# BMS_Master.net
KiCad netlist of a schematic drawn in EAGLE
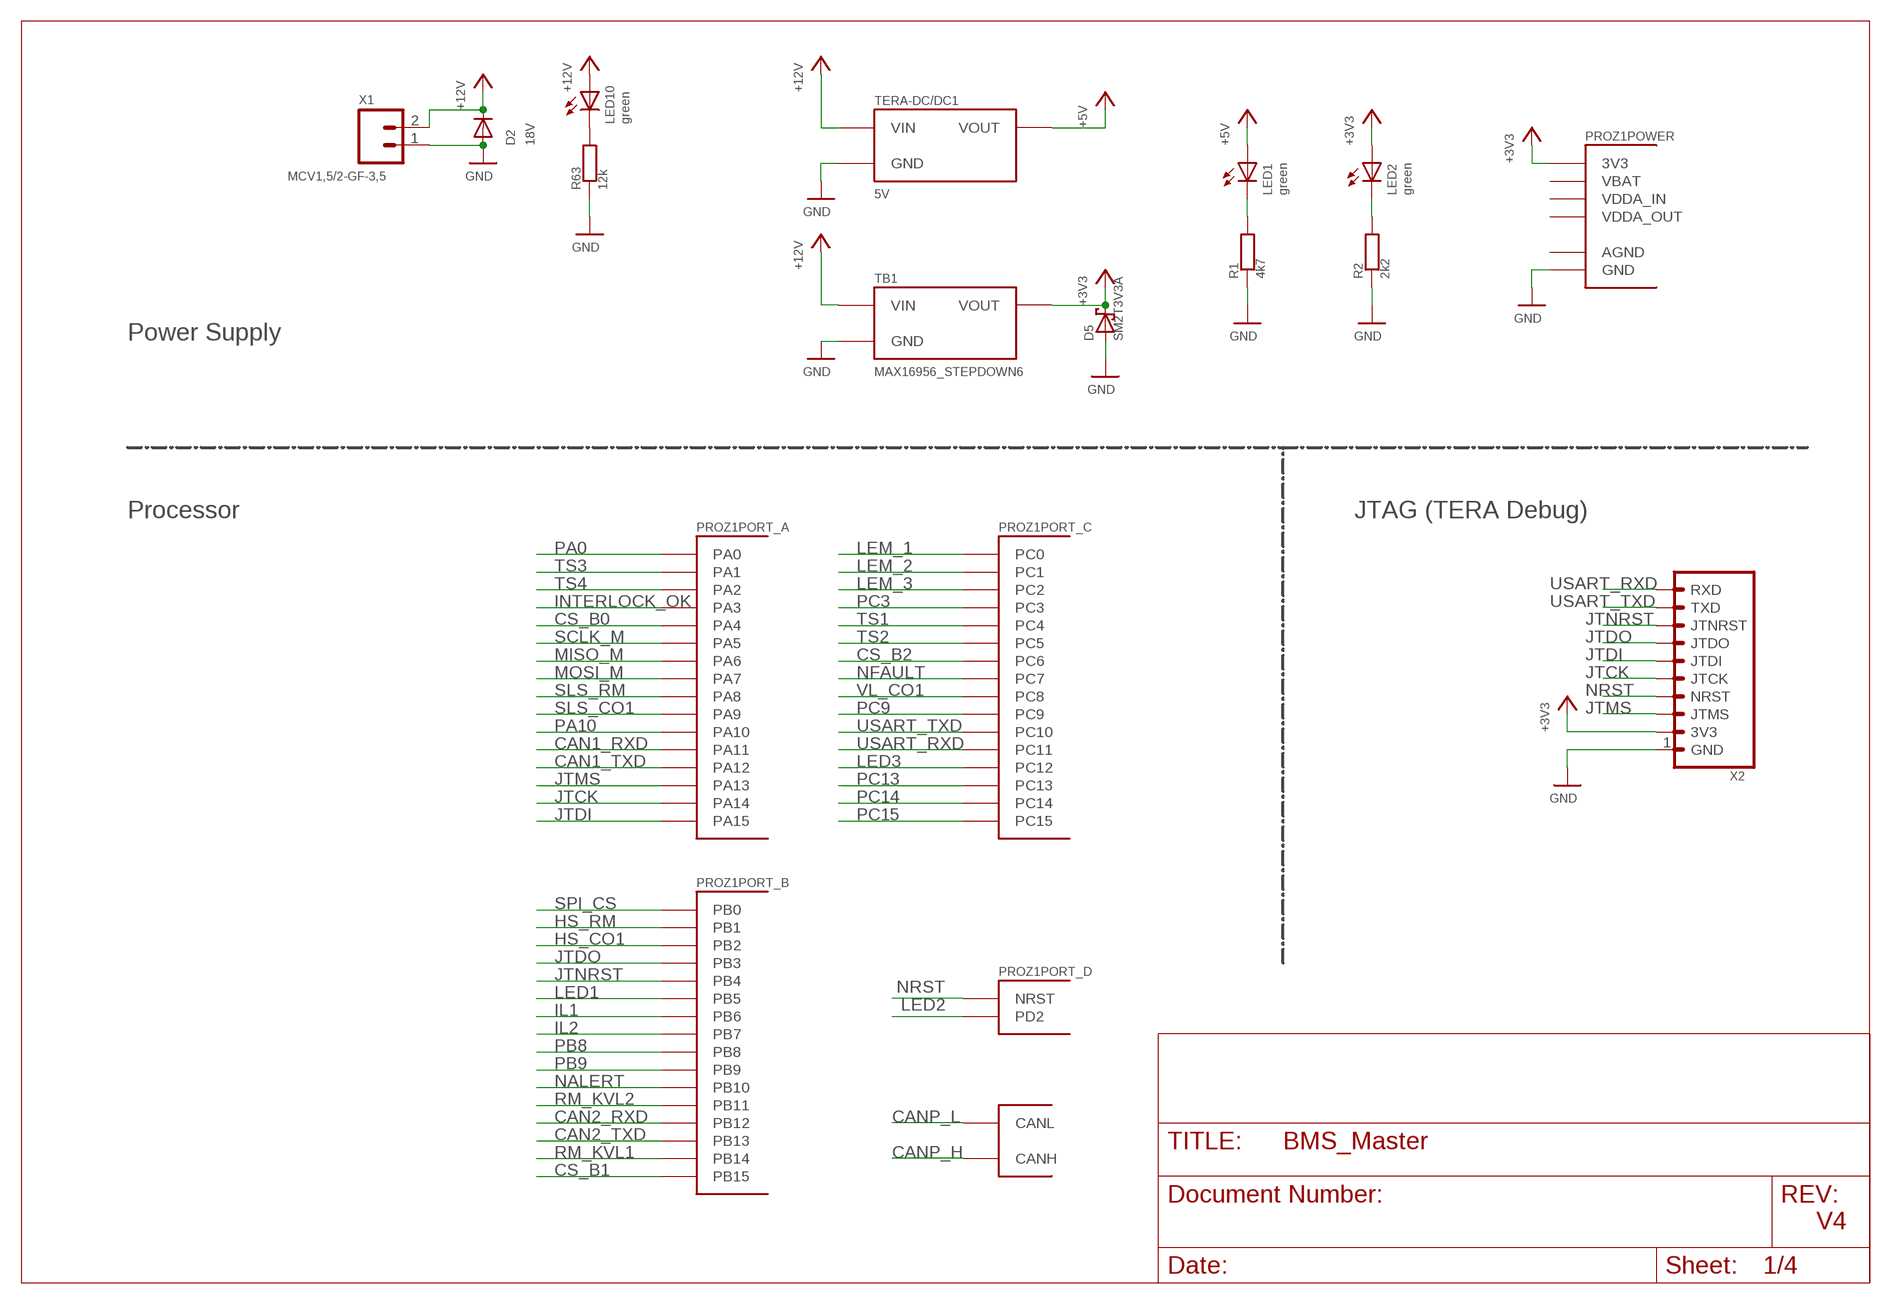
[diagram p0: schematic, sheet 1]
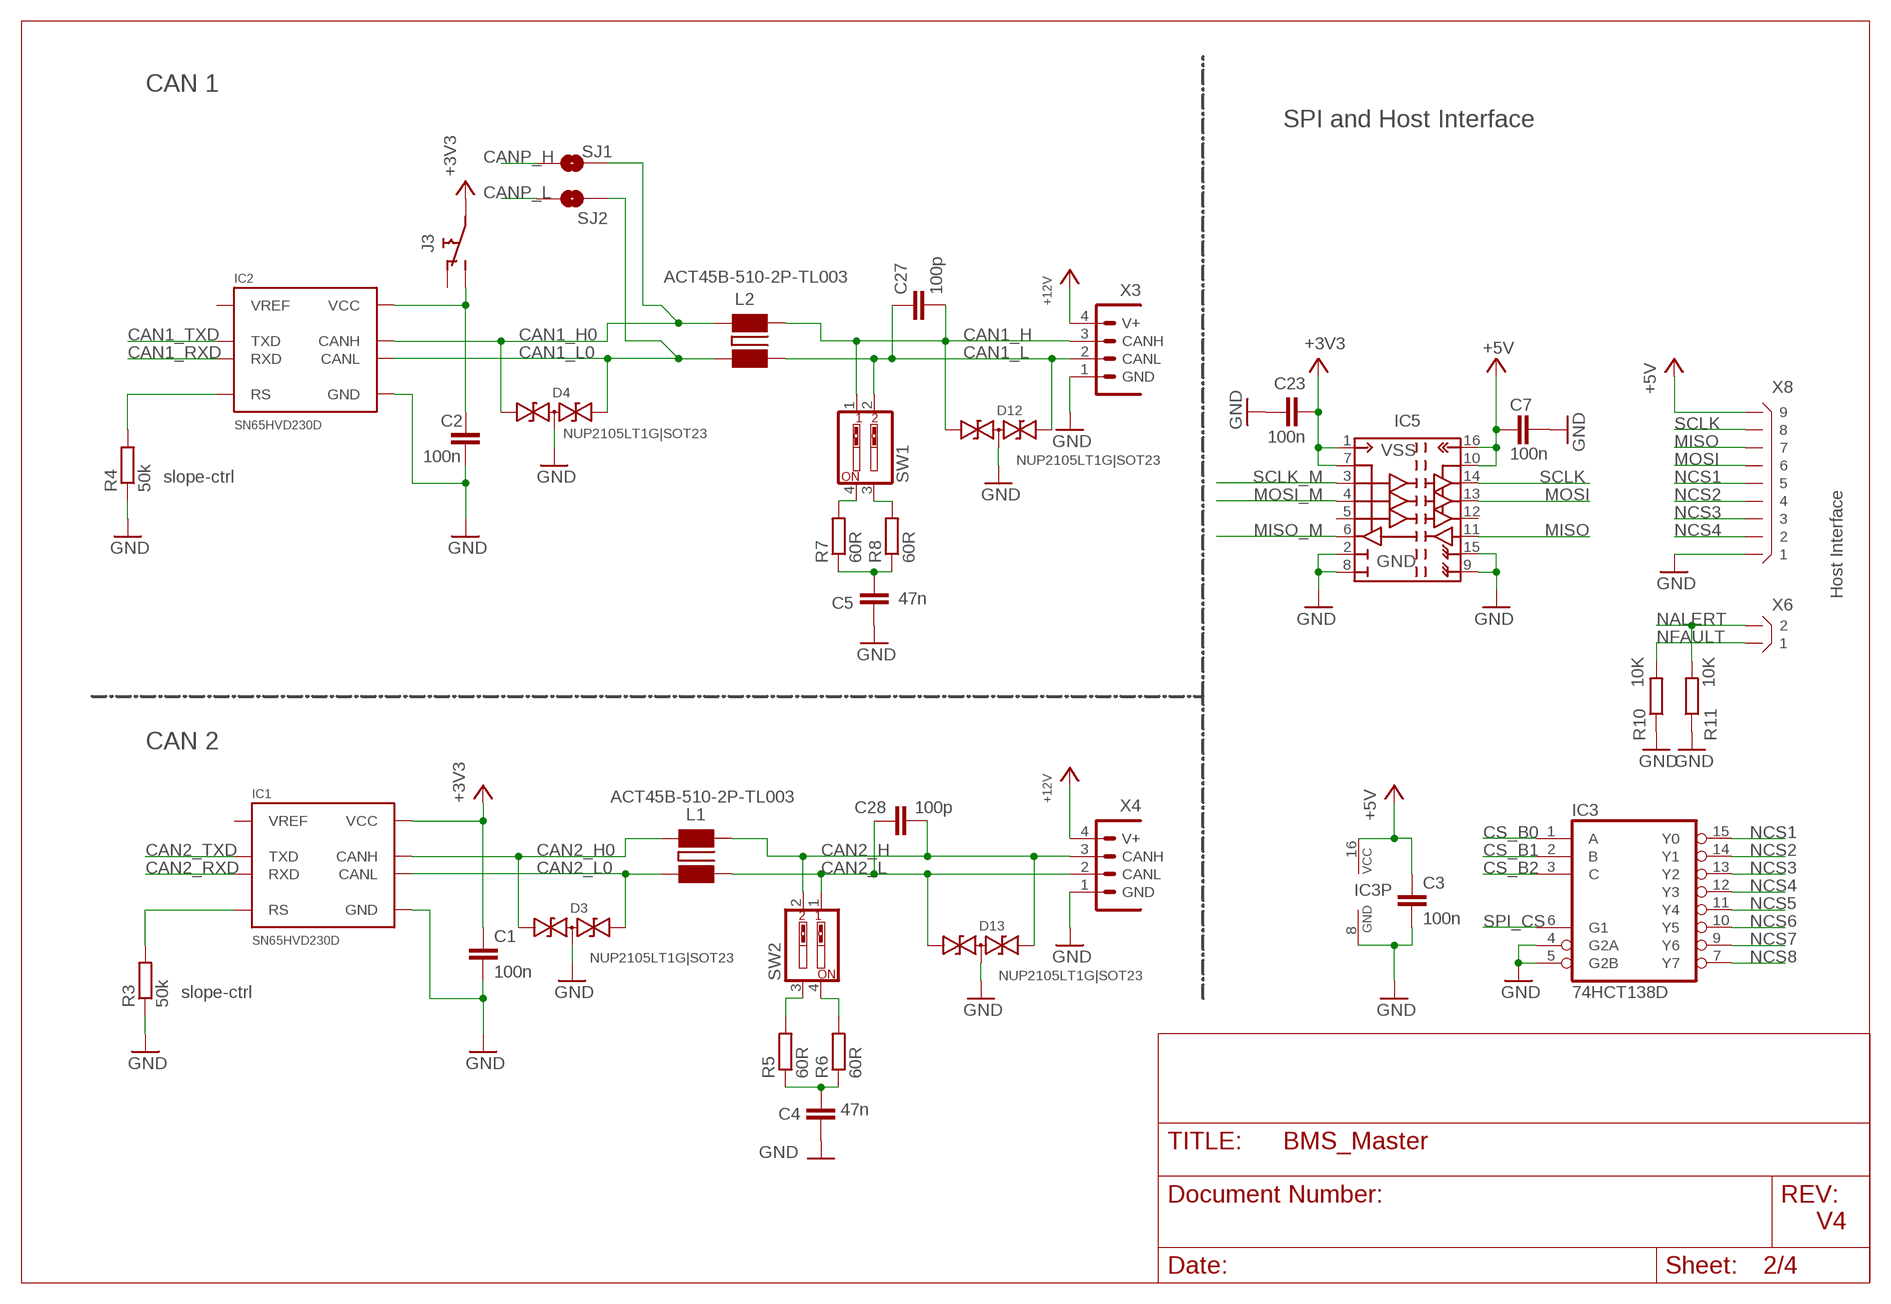
[diagram p1: schematic, sheet 2]
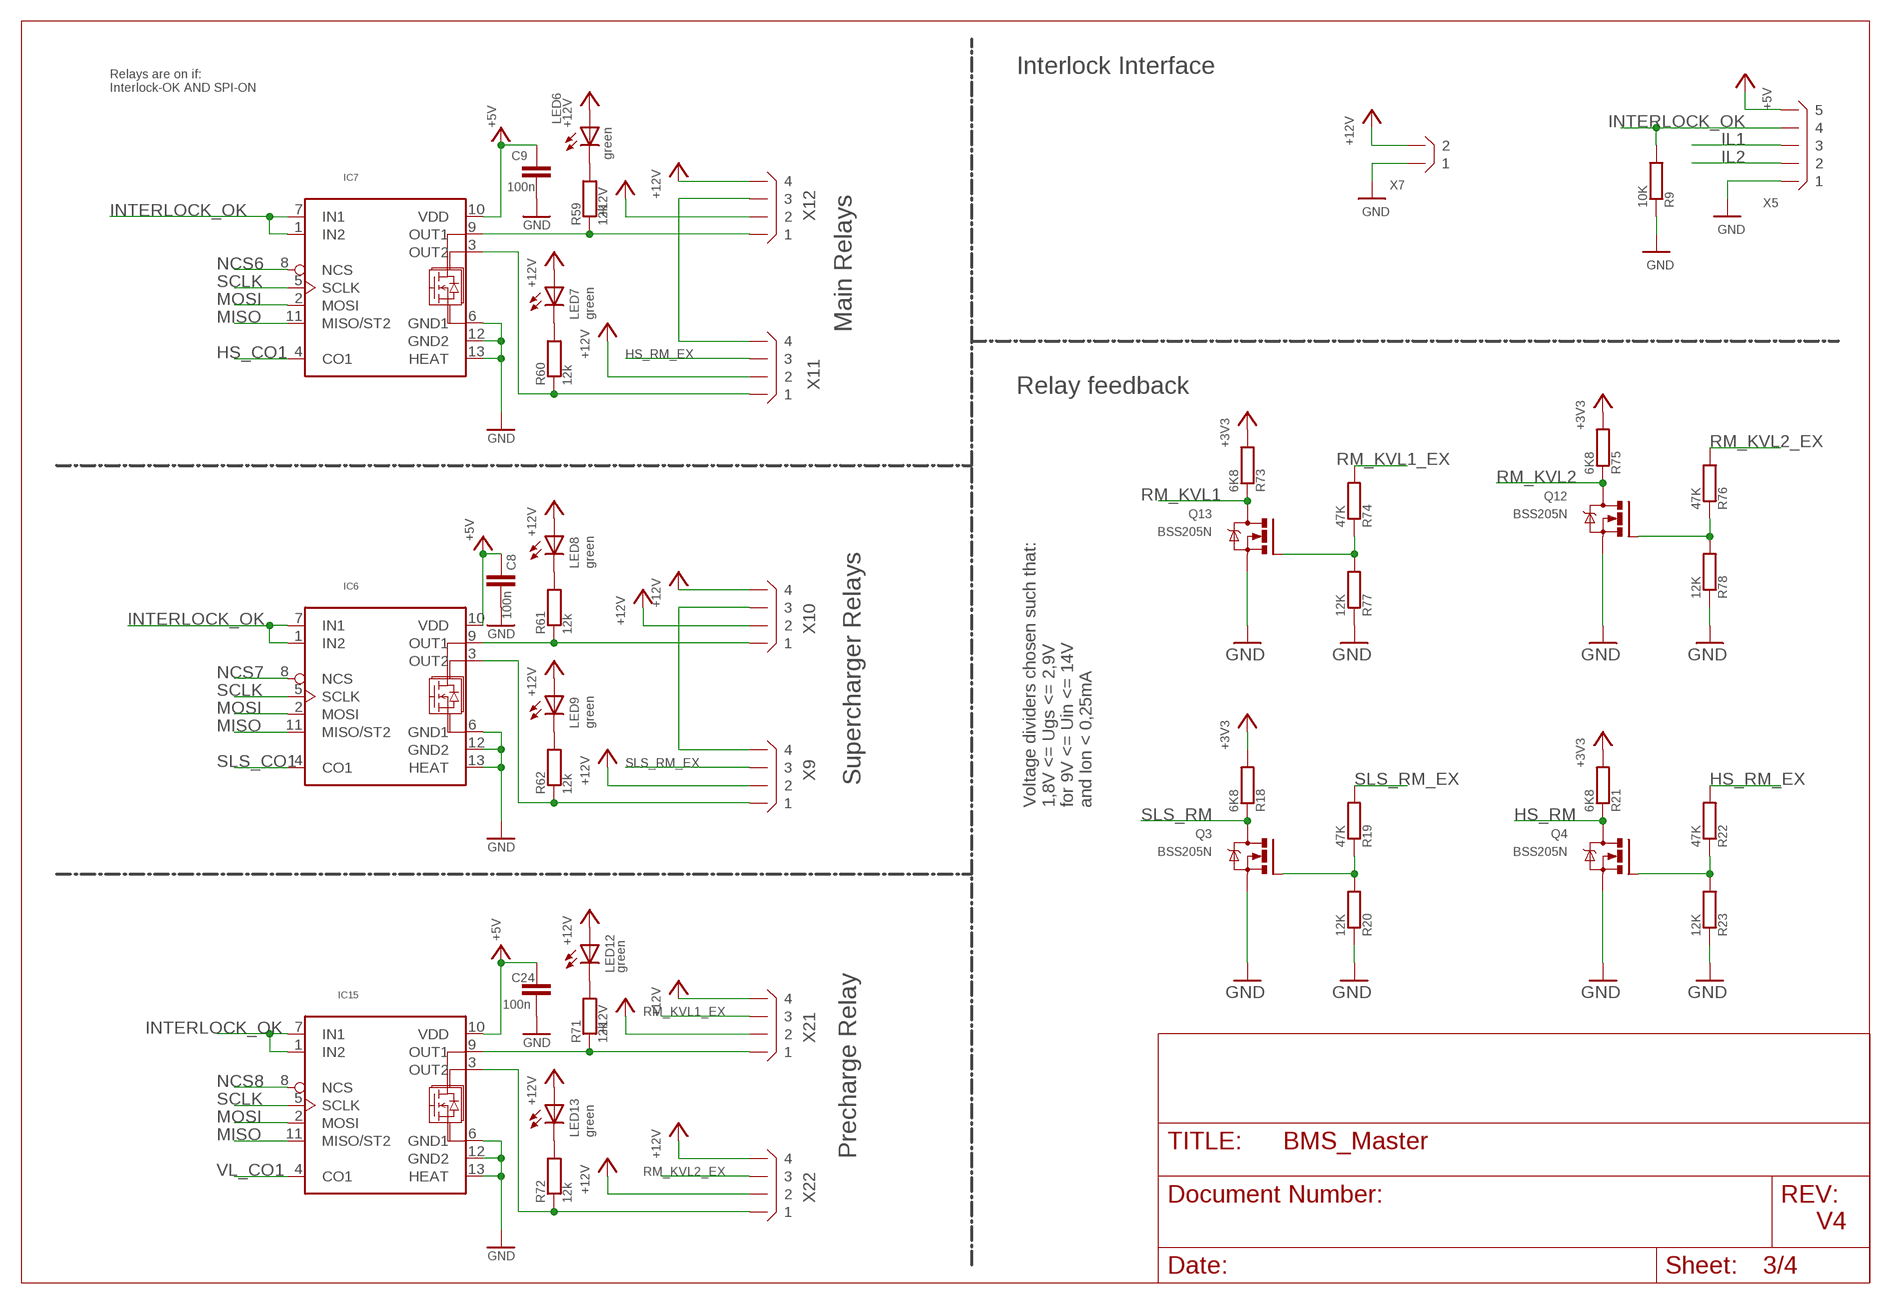
[diagram p2: schematic, sheet 3]
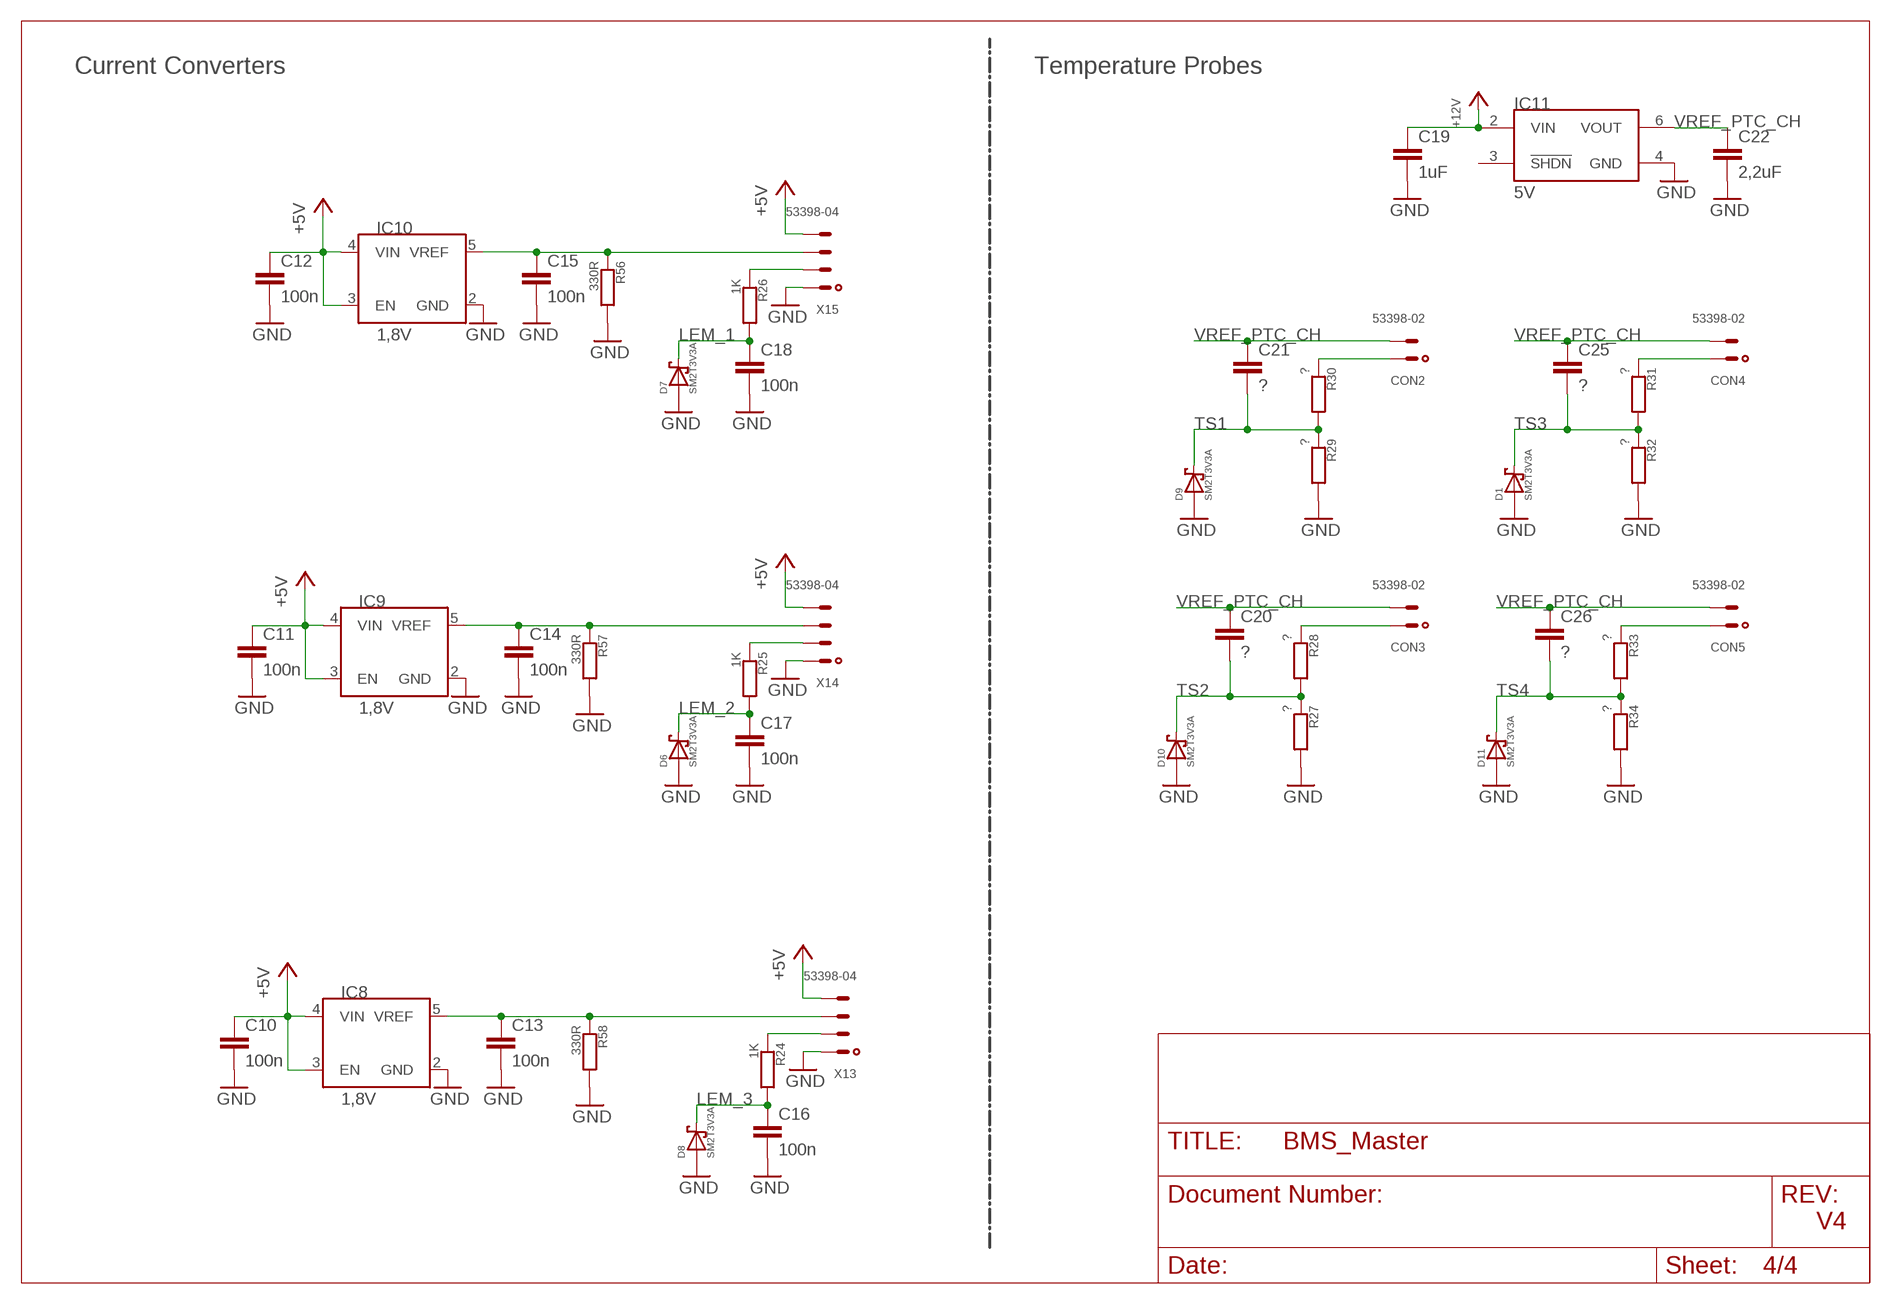
[diagram p3: schematic, sheet 4]

(export (version "E")
  (design (tool "Eeschema 10.0.6"))
  (components
    (comp (ref "D2")
      (value "18V")
      (footprint "eagle-import:DO214AA")
      (libsource (lib "eagle-import") (part "DIODE-DO214AA"))
    )
    (comp (ref "D5")
      (value "SM2T3V3A")
      (footprint "eagle-import:SM2T3V3A")
      (libsource (lib "eagle-import") (part "SM2T3V3A"))
    )
    (comp (ref "LED1")
      (value "green")
      (footprint "eagle-import:CHIP-LED0805")
      (libsource (lib "eagle-import") (part "LEDCHIP-LED0805"))
    )
    (comp (ref "LED2")
      (value "green")
      (footprint "eagle-import:CHIP-LED0805")
      (libsource (lib "eagle-import") (part "LEDCHIP-LED0805"))
    )
    (comp (ref "LED10")
      (value "green")
      (footprint "eagle-import:CHIP-LED0805")
      (libsource (lib "eagle-import") (part "LEDCHIP-LED0805"))
    )
    (comp (ref "PROZ1")
      (value "STM32F4_PROZESSORBOARDRPZ")
      (footprint "eagle-import:STM32F4_PROZESSORBOARD")
      (libsource (lib "eagle-import") (part "STM32F4_PROZESSORBOARDRPZ"))
    )
    (comp (ref "R1")
      (value "4k7")
      (footprint "eagle-import:R0805")
      (libsource (lib "eagle-import") (part "R"))
    )
    (comp (ref "R2")
      (value "2k2")
      (footprint "eagle-import:R0805")
      (libsource (lib "eagle-import") (part "R"))
    )
    (comp (ref "R63")
      (value "12k")
      (footprint "eagle-import:R0805")
      (libsource (lib "eagle-import") (part "R"))
    )
    (comp (ref "TB1")
      (value "MAX16956_STEPDOWN6")
      (footprint "eagle-import:MAX16956_STEPDOWN6")
      (libsource (lib "eagle-import") (part "MAX16956_STEPDOWN6"))
    )
    (comp (ref "TERA-DC/DC1")
      (value "5V")
      (footprint "eagle-import:MAX5035_STEPDOWN3")
      (libsource (lib "eagle-import") (part "MAX5035_STEPDOWN3"))
    )
    (comp (ref "X1")
      (value "MCV1,5/2-GF-3,5")
      (footprint "eagle-import:MCV1,5_2-GF-3,5")
      (libsource (lib "eagle-import") (part "MCV1,5/2-GF-3,5"))
    )
    (comp (ref "X2")
      (value "TERA-PROG-DEBUG-10GERADE")
      (footprint "eagle-import:90130-1110")
      (libsource (lib "eagle-import") (part "TERA-PROG-DEBUG-10GERADE"))
    )
    (comp (ref "C8")
      (value "100n")
      (footprint "eagle-import:C0603")
      (libsource (lib "eagle-import") (part "C-EUC0603"))
    )
    (comp (ref "C9")
      (value "100n")
      (footprint "eagle-import:C0603")
      (libsource (lib "eagle-import") (part "C-EUC0603"))
    )
    (comp (ref "C24")
      (value "100n")
      (footprint "eagle-import:C0603")
      (libsource (lib "eagle-import") (part "C-EUC0603"))
    )
    (comp (ref "IC6")
      (value "TLE8102SGN")
      (footprint "eagle-import:INF-PG-DSO-12-11_N_1PRIMARY")
      (libsource (lib "eagle-import") (part "TLE8102SGN"))
    )
    (comp (ref "IC7")
      (value "TLE8102SGN")
      (footprint "eagle-import:INF-PG-DSO-12-11_N_1PRIMARY")
      (libsource (lib "eagle-import") (part "TLE8102SGN"))
    )
    (comp (ref "IC15")
      (value "TLE8102SGN")
      (footprint "eagle-import:INF-PG-DSO-12-11_N_1PRIMARY")
      (libsource (lib "eagle-import") (part "TLE8102SGN"))
    )
    (comp (ref "LED6")
      (value "green")
      (footprint "eagle-import:CHIP-LED0805")
      (libsource (lib "eagle-import") (part "LEDCHIP-LED0805"))
    )
    (comp (ref "LED7")
      (value "green")
      (footprint "eagle-import:CHIP-LED0805")
      (libsource (lib "eagle-import") (part "LEDCHIP-LED0805"))
    )
    (comp (ref "LED8")
      (value "green")
      (footprint "eagle-import:CHIP-LED0805")
      (libsource (lib "eagle-import") (part "LEDCHIP-LED0805"))
    )
    (comp (ref "LED9")
      (value "green")
      (footprint "eagle-import:CHIP-LED0805")
      (libsource (lib "eagle-import") (part "LEDCHIP-LED0805"))
    )
    (comp (ref "LED12")
      (value "green")
      (footprint "eagle-import:CHIP-LED0805")
      (libsource (lib "eagle-import") (part "LEDCHIP-LED0805"))
    )
    (comp (ref "LED13")
      (value "green")
      (footprint "eagle-import:CHIP-LED0805")
      (libsource (lib "eagle-import") (part "LEDCHIP-LED0805"))
    )
    (comp (ref "Q3")
      (value "BSS205N")
      (footprint "eagle-import:SOT23")
      (libsource (lib "eagle-import") (part "BSS205N"))
    )
    (comp (ref "Q4")
      (value "BSS205N")
      (footprint "eagle-import:SOT23")
      (libsource (lib "eagle-import") (part "BSS205N"))
    )
    (comp (ref "Q12")
      (value "BSS205N")
      (footprint "eagle-import:SOT23")
      (libsource (lib "eagle-import") (part "BSS205N"))
    )
    (comp (ref "Q13")
      (value "BSS205N")
      (footprint "eagle-import:SOT23")
      (libsource (lib "eagle-import") (part "BSS205N"))
    )
    (comp (ref "R9")
      (value "10K")
      (footprint "eagle-import:R0805")
      (libsource (lib "eagle-import") (part "R"))
    )
    (comp (ref "R18")
      (value "6K8")
      (footprint "eagle-import:R0603")
      (libsource (lib "eagle-import") (part "R0603"))
    )
    (comp (ref "R19")
      (value "47K")
      (footprint "eagle-import:R0805")
      (libsource (lib "eagle-import") (part "R"))
    )
    (comp (ref "R20")
      (value "12K")
      (footprint "eagle-import:R0805")
      (libsource (lib "eagle-import") (part "R"))
    )
    (comp (ref "R21")
      (value "6K8")
      (footprint "eagle-import:R0603")
      (libsource (lib "eagle-import") (part "R0603"))
    )
    (comp (ref "R22")
      (value "47K")
      (footprint "eagle-import:R0805")
      (libsource (lib "eagle-import") (part "R"))
    )
    (comp (ref "R23")
      (value "12K")
      (footprint "eagle-import:R0805")
      (libsource (lib "eagle-import") (part "R"))
    )
    (comp (ref "R59")
      (value "12k")
      (footprint "eagle-import:R0805")
      (libsource (lib "eagle-import") (part "R"))
    )
    (comp (ref "R60")
      (value "12k")
      (footprint "eagle-import:R0805")
      (libsource (lib "eagle-import") (part "R"))
    )
    (comp (ref "R61")
      (value "12k")
      (footprint "eagle-import:R0805")
      (libsource (lib "eagle-import") (part "R"))
    )
    (comp (ref "R62")
      (value "12k")
      (footprint "eagle-import:R0805")
      (libsource (lib "eagle-import") (part "R"))
    )
    (comp (ref "R71")
      (value "12k")
      (footprint "eagle-import:R0805")
      (libsource (lib "eagle-import") (part "R"))
    )
    (comp (ref "R72")
      (value "12k")
      (footprint "eagle-import:R0805")
      (libsource (lib "eagle-import") (part "R"))
    )
    (comp (ref "R73")
      (value "6K8")
      (footprint "eagle-import:R0805")
      (libsource (lib "eagle-import") (part "R"))
    )
    (comp (ref "R74")
      (value "47K")
      (footprint "eagle-import:R0805")
      (libsource (lib "eagle-import") (part "R"))
    )
    (comp (ref "R75")
      (value "6K8")
      (footprint "eagle-import:R0805")
      (libsource (lib "eagle-import") (part "R"))
    )
    (comp (ref "R76")
      (value "47K")
      (footprint "eagle-import:R0805")
      (libsource (lib "eagle-import") (part "R"))
    )
    (comp (ref "R77")
      (value "12K")
      (footprint "eagle-import:R0805")
      (libsource (lib "eagle-import") (part "R"))
    )
    (comp (ref "R78")
      (value "12K")
      (footprint "eagle-import:R0805")
      (libsource (lib "eagle-import") (part "R"))
    )
    (comp (ref "X5")
      (value "B5B-XH")
      (footprint "eagle-import:B5B-XH")
      (libsource (lib "eagle-import") (part "?5B-XHB"))
    )
    (comp (ref "X7")
      (value "B2B-XH")
      (footprint "eagle-import:B2B-XH")
      (libsource (lib "eagle-import") (part "?2B-XHB"))
    )
    (comp (ref "X9")
      (value "B4B-XH")
      (footprint "eagle-import:B4B-XH")
      (libsource (lib "eagle-import") (part "?4B-XHB"))
    )
    (comp (ref "X10")
      (value "B4B-XH")
      (footprint "eagle-import:B4B-XH")
      (libsource (lib "eagle-import") (part "?4B-XHB"))
    )
    (comp (ref "X11")
      (value "B4B-XH")
      (footprint "eagle-import:B4B-XH")
      (libsource (lib "eagle-import") (part "?4B-XHB"))
    )
    (comp (ref "X12")
      (value "B4B-XH")
      (footprint "eagle-import:B4B-XH")
      (libsource (lib "eagle-import") (part "?4B-XHB"))
    )
    (comp (ref "X21")
      (value "B4B-XH")
      (footprint "eagle-import:B4B-XH")
      (libsource (lib "eagle-import") (part "?4B-XHB"))
    )
    (comp (ref "X22")
      (value "B4B-XH")
      (footprint "eagle-import:B4B-XH")
      (libsource (lib "eagle-import") (part "?4B-XHB"))
    )
    (comp (ref "C10")
      (value "100n")
      (footprint "eagle-import:C0805")
      (libsource (lib "eagle-import") (part "C-EUC0805"))
    )
    (comp (ref "C11")
      (value "100n")
      (footprint "eagle-import:C0805")
      (libsource (lib "eagle-import") (part "C-EUC0805"))
    )
    (comp (ref "C12")
      (value "100n")
      (footprint "eagle-import:C0805")
      (libsource (lib "eagle-import") (part "C-EUC0805"))
    )
    (comp (ref "C13")
      (value "100n")
      (footprint "eagle-import:C0805")
      (libsource (lib "eagle-import") (part "C-EUC0805"))
    )
    (comp (ref "C14")
      (value "100n")
      (footprint "eagle-import:C0805")
      (libsource (lib "eagle-import") (part "C-EUC0805"))
    )
    (comp (ref "C15")
      (value "100n")
      (footprint "eagle-import:C0805")
      (libsource (lib "eagle-import") (part "C-EUC0805"))
    )
    (comp (ref "C16")
      (value "100n")
      (footprint "eagle-import:C0805")
      (libsource (lib "eagle-import") (part "C-EUC0805"))
    )
    (comp (ref "C17")
      (value "100n")
      (footprint "eagle-import:C0805")
      (libsource (lib "eagle-import") (part "C-EUC0805"))
    )
    (comp (ref "C18")
      (value "100n")
      (footprint "eagle-import:C0805")
      (libsource (lib "eagle-import") (part "C-EUC0805"))
    )
    (comp (ref "C19")
      (value "1uF")
      (footprint "eagle-import:C0805")
      (libsource (lib "eagle-import") (part "C-EUC0805"))
    )
    (comp (ref "C20")
      (value "?")
      (footprint "eagle-import:C0603")
      (libsource (lib "eagle-import") (part "C-EUC0603"))
    )
    (comp (ref "C21")
      (value "?")
      (footprint "eagle-import:C0603")
      (libsource (lib "eagle-import") (part "C-EUC0603"))
    )
    (comp (ref "C22")
      (value "2,2uF")
      (footprint "eagle-import:C0805")
      (libsource (lib "eagle-import") (part "C-EUC0805"))
    )
    (comp (ref "C25")
      (value "?")
      (footprint "eagle-import:C0603")
      (libsource (lib "eagle-import") (part "C-EUC0603"))
    )
    (comp (ref "C26")
      (value "?")
      (footprint "eagle-import:C0603")
      (libsource (lib "eagle-import") (part "C-EUC0603"))
    )
    (comp (ref "CON2")
      (value "53398-02")
      (footprint "eagle-import:53398-02")
      (libsource (lib "eagle-import") (part "53?-02398"))
    )
    (comp (ref "CON3")
      (value "53398-02")
      (footprint "eagle-import:53398-02")
      (libsource (lib "eagle-import") (part "53?-02398"))
    )
    (comp (ref "CON4")
      (value "53398-02")
      (footprint "eagle-import:53398-02")
      (libsource (lib "eagle-import") (part "53?-02398"))
    )
    (comp (ref "CON5")
      (value "53398-02")
      (footprint "eagle-import:53398-02")
      (libsource (lib "eagle-import") (part "53?-02398"))
    )
    (comp (ref "D1")
      (value "SM2T3V3A")
      (footprint "eagle-import:SM2T3V3A")
      (libsource (lib "eagle-import") (part "SM2T3V3A"))
    )
    (comp (ref "D6")
      (value "SM2T3V3A")
      (footprint "eagle-import:SM2T3V3A")
      (libsource (lib "eagle-import") (part "SM2T3V3A"))
    )
    (comp (ref "D7")
      (value "SM2T3V3A")
      (footprint "eagle-import:SM2T3V3A")
      (libsource (lib "eagle-import") (part "SM2T3V3A"))
    )
    (comp (ref "D8")
      (value "SM2T3V3A")
      (footprint "eagle-import:SM2T3V3A")
      (libsource (lib "eagle-import") (part "SM2T3V3A"))
    )
    (comp (ref "D9")
      (value "SM2T3V3A")
      (footprint "eagle-import:SM2T3V3A")
      (libsource (lib "eagle-import") (part "SM2T3V3A"))
    )
    (comp (ref "D10")
      (value "SM2T3V3A")
      (footprint "eagle-import:SM2T3V3A")
      (libsource (lib "eagle-import") (part "SM2T3V3A"))
    )
    (comp (ref "D11")
      (value "SM2T3V3A")
      (footprint "eagle-import:SM2T3V3A")
      (libsource (lib "eagle-import") (part "SM2T3V3A"))
    )
    (comp (ref "IC8")
      (value "1,8V")
      (footprint "eagle-import:SOT23-5L")
      (libsource (lib "eagle-import") (part "LM4132L"))
    )
    (comp (ref "IC9")
      (value "1,8V")
      (footprint "eagle-import:SOT23-5L")
      (libsource (lib "eagle-import") (part "LM4132L"))
    )
    (comp (ref "IC10")
      (value "1,8V")
      (footprint "eagle-import:SOT23-5L")
      (libsource (lib "eagle-import") (part "LM4132L"))
    )
    (comp (ref "IC11")
      (value "5V")
      (footprint "eagle-import:SO08")
      (libsource (lib "eagle-import") (part "LT1461"))
    )
    (comp (ref "R24")
      (value "1K")
      (footprint "eagle-import:R0805")
      (libsource (lib "eagle-import") (part "R"))
    )
    (comp (ref "R25")
      (value "1K")
      (footprint "eagle-import:R0805")
      (libsource (lib "eagle-import") (part "R"))
    )
    (comp (ref "R26")
      (value "1K")
      (footprint "eagle-import:R0805")
      (libsource (lib "eagle-import") (part "R"))
    )
    (comp (ref "R27")
      (value "?")
      (footprint "eagle-import:R0603")
      (libsource (lib "eagle-import") (part "R0603"))
    )
    (comp (ref "R28")
      (value "?")
      (footprint "eagle-import:R0603")
      (libsource (lib "eagle-import") (part "R0603"))
    )
    (comp (ref "R29")
      (value "?")
      (footprint "eagle-import:R0603")
      (libsource (lib "eagle-import") (part "R0603"))
    )
    (comp (ref "R30")
      (value "?")
      (footprint "eagle-import:R0603")
      (libsource (lib "eagle-import") (part "R0603"))
    )
    (comp (ref "R31")
      (value "?")
      (footprint "eagle-import:R0603")
      (libsource (lib "eagle-import") (part "R0603"))
    )
    (comp (ref "R32")
      (value "?")
      (footprint "eagle-import:R0603")
      (libsource (lib "eagle-import") (part "R0603"))
    )
    (comp (ref "R33")
      (value "?")
      (footprint "eagle-import:R0603")
      (libsource (lib "eagle-import") (part "R0603"))
    )
    (comp (ref "R34")
      (value "?")
      (footprint "eagle-import:R0603")
      (libsource (lib "eagle-import") (part "R0603"))
    )
    (comp (ref "R56")
      (value "330R")
      (footprint "eagle-import:R0805")
      (libsource (lib "eagle-import") (part "R"))
    )
    (comp (ref "R57")
      (value "330R")
      (footprint "eagle-import:R0805")
      (libsource (lib "eagle-import") (part "R"))
    )
    (comp (ref "R58")
      (value "330R")
      (footprint "eagle-import:R0805")
      (libsource (lib "eagle-import") (part "R"))
    )
    (comp (ref "X13")
      (value "53398-04")
      (footprint "eagle-import:53398-04")
      (libsource (lib "eagle-import") (part "53?-04398"))
    )
    (comp (ref "X14")
      (value "53398-04")
      (footprint "eagle-import:53398-04")
      (libsource (lib "eagle-import") (part "53?-04398"))
    )
    (comp (ref "X15")
      (value "53398-04")
      (footprint "eagle-import:53398-04")
      (libsource (lib "eagle-import") (part "53?-04398"))
    )
    (comp (ref "C1")
      (value "100n")
      (footprint "eagle-import:C0805")
      (libsource (lib "eagle-import") (part "C-EUC0805"))
    )
    (comp (ref "C2")
      (value "100n")
      (footprint "eagle-import:C0805")
      (libsource (lib "eagle-import") (part "C-EUC0805"))
    )
    (comp (ref "C3")
      (value "100n")
      (footprint "eagle-import:C0805")
      (libsource (lib "eagle-import") (part "C-EUC0805"))
    )
    (comp (ref "C4")
      (value "47n")
      (footprint "eagle-import:C0603")
      (libsource (lib "eagle-import") (part "C-EUC0603"))
    )
    (comp (ref "C5")
      (value "47n")
      (footprint "eagle-import:C0603")
      (libsource (lib "eagle-import") (part "C-EUC0603"))
    )
    (comp (ref "C7")
      (value "100n")
      (footprint "eagle-import:C0603")
      (libsource (lib "eagle-import") (part "C0603"))
    )
    (comp (ref "C23")
      (value "100n")
      (footprint "eagle-import:C0603")
      (libsource (lib "eagle-import") (part "C0603"))
    )
    (comp (ref "C27")
      (value "100p")
      (footprint "eagle-import:C0603")
      (libsource (lib "eagle-import") (part "C-EUC0603"))
    )
    (comp (ref "C28")
      (value "100p")
      (footprint "eagle-import:C0603")
      (libsource (lib "eagle-import") (part "C-EUC0603"))
    )
    (comp (ref "D3")
      (value "NUP2105LT1G|SOT23")
      (footprint "eagle-import:SOT23")
      (libsource (lib "eagle-import") (part "NUP2105LT1G|SOT23"))
    )
    (comp (ref "D4")
      (value "NUP2105LT1G|SOT23")
      (footprint "eagle-import:SOT23")
      (libsource (lib "eagle-import") (part "NUP2105LT1G|SOT23"))
    )
    (comp (ref "D12")
      (value "NUP2105LT1G|SOT23")
      (footprint "eagle-import:SOT23")
      (libsource (lib "eagle-import") (part "NUP2105LT1G|SOT23"))
    )
    (comp (ref "D13")
      (value "NUP2105LT1G|SOT23")
      (footprint "eagle-import:SOT23")
      (libsource (lib "eagle-import") (part "NUP2105LT1G|SOT23"))
    )
    (comp (ref "IC1")
      (value "SN65HVD230D")
      (footprint "eagle-import:SO08")
      (libsource (lib "eagle-import") (part "SN65HVD23D0"))
    )
    (comp (ref "IC2")
      (value "SN65HVD230D")
      (footprint "eagle-import:SO08")
      (libsource (lib "eagle-import") (part "SN65HVD23D0"))
    )
    (comp (ref "IC3")
      (value "74HCT138D")
      (footprint "eagle-import:SO16")
      (libsource (lib "eagle-import") (part "74138DHCT"))
    )
    (comp (ref "IC5")
      (value "ISO7241")
      (footprint "eagle-import:R-PDSO-G16")
      (libsource (lib "eagle-import") (part "ISO7241"))
    )
    (comp (ref "J3")
      (value "JUMPER_SWITCHS")
      (footprint "eagle-import:J_OR_S")
      (libsource (lib "eagle-import") (part "JUMPER_SWITCHS"))
    )
    (comp (ref "L1")
      (value "ACT45B-510-2P-TL003")
      (footprint "eagle-import:ACT45B")
      (libsource (lib "eagle-import") (part "ACT45B-510-2P-TL003"))
    )
    (comp (ref "L2")
      (value "ACT45B-510-2P-TL003")
      (footprint "eagle-import:ACT45B")
      (libsource (lib "eagle-import") (part "ACT45B-510-2P-TL003"))
    )
    (comp (ref "R3")
      (value "50k")
      (footprint "eagle-import:R0805")
      (libsource (lib "eagle-import") (part "R-EU_R0805"))
    )
    (comp (ref "R4")
      (value "50k")
      (footprint "eagle-import:R0805")
      (libsource (lib "eagle-import") (part "R-EU_R0805"))
    )
    (comp (ref "R5")
      (value "60R")
      (footprint "eagle-import:R0603")
      (libsource (lib "eagle-import") (part "R-EU_R0603"))
    )
    (comp (ref "R6")
      (value "60R")
      (footprint "eagle-import:R0603")
      (libsource (lib "eagle-import") (part "R-EU_R0603"))
    )
    (comp (ref "R7")
      (value "60R")
      (footprint "eagle-import:R0603")
      (libsource (lib "eagle-import") (part "R-EU_R0603"))
    )
    (comp (ref "R8")
      (value "60R")
      (footprint "eagle-import:R0603")
      (libsource (lib "eagle-import") (part "R-EU_R0603"))
    )
    (comp (ref "R10")
      (value "10K")
      (footprint "eagle-import:R0603")
      (libsource (lib "eagle-import") (part "R-EU_R0603"))
    )
    (comp (ref "R11")
      (value "10K")
      (footprint "eagle-import:R0603")
      (libsource (lib "eagle-import") (part "R-EU_R0603"))
    )
    (comp (ref "SJ1")
      (value "SOLDERJUMPERNO")
      (footprint "eagle-import:SJ_2S-NO")
      (libsource (lib "eagle-import") (part "SOLDERJUMPERNO"))
    )
    (comp (ref "SJ2")
      (value "SOLDERJUMPERNO")
      (footprint "eagle-import:SJ_2S-NO")
      (libsource (lib "eagle-import") (part "SOLDERJUMPERNO"))
    )
    (comp (ref "SW1")
      (value "DIP_SWITCH_DIP2")
      (footprint "eagle-import:DIPSWITCH-02")
      (libsource (lib "eagle-import") (part "DIP_SWITCH_DIP2"))
    )
    (comp (ref "SW2")
      (value "DIP_SWITCH_DIP2")
      (footprint "eagle-import:DIPSWITCH-02")
      (libsource (lib "eagle-import") (part "DIP_SWITCH_DIP2"))
    )
    (comp (ref "X3")
      (value "CIOC_4-1-FV-A_CAN-BELEGUNG")
      (footprint "eagle-import:CIOC_4-1-FV")
      (libsource (lib "eagle-import") (part "CIOC_4-1-FV-A_CAN-BELEGUNG"))
    )
    (comp (ref "X4")
      (value "CIOC_4-1-FV-A_CAN-BELEGUNG")
      (footprint "eagle-import:CIOC_4-1-FV")
      (libsource (lib "eagle-import") (part "CIOC_4-1-FV-A_CAN-BELEGUNG"))
    )
    (comp (ref "X6")
      (value "B2B-XH")
      (footprint "eagle-import:B2B-XH")
      (libsource (lib "eagle-import") (part "?2B-XHB"))
    )
    (comp (ref "X8")
      (value "B9B-XH")
      (footprint "eagle-import:B9B-XH")
      (libsource (lib "eagle-import") (part "?9B-XHB"))
    )
  )
  (nets
    (net (code "1") (name "+3V3") (class "Default")
      (node (ref "C1") (pin "1") (pinfunction "1_1") (pintype "passive"))
      (node (ref "C23") (pin "2") (pinfunction "2_2") (pintype "passive"))
      (node (ref "D5") (pin "P$2") (pinfunction "P$2_P$2") (pintype "bidirectional"))
      (node (ref "IC1") (pin "3") (pinfunction "VCC_3") (pintype "power_in"))
      (node (ref "IC5") (pin "1") (pinfunction "VCC1_1") (pintype "bidirectional"))
      (node (ref "IC5") (pin "7") (pinfunction "EN1_7") (pintype "bidirectional"))
      (node (ref "J3") (pin "P$1") (pinfunction "P$1_P$1") (pintype "bidirectional"))
      (node (ref "LED2") (pin "A") (pinfunction "A_A") (pintype "passive"))
      (node (ref "PROZ1") (pin "45") (pinfunction "3V3_45") (pintype "passive"))
      (node (ref "PROZ1") (pin "46") (pinfunction "3V3_46") (pintype "passive"))
      (node (ref "R18") (pin "2") (pinfunction "2_2") (pintype "passive"))
      (node (ref "R21") (pin "2") (pinfunction "2_2") (pintype "passive"))
      (node (ref "R73") (pin "2") (pinfunction "2_2") (pintype "passive"))
      (node (ref "R75") (pin "2") (pinfunction "2_2") (pintype "passive"))
      (node (ref "TB1") (pin "VOUT") (pinfunction "VOUT_VOUT") (pintype "passive"))
      (node (ref "X2") (pin "2") (pinfunction "3V3_2") (pintype "passive"))
    )
    (net (code "2") (name "+5V") (class "Default")
      (node (ref "C10") (pin "1") (pinfunction "1_1") (pintype "passive"))
      (node (ref "C11") (pin "1") (pinfunction "1_1") (pintype "passive"))
      (node (ref "C12") (pin "1") (pinfunction "1_1") (pintype "passive"))
      (node (ref "C24") (pin "1") (pinfunction "1_1") (pintype "passive"))
      (node (ref "C3") (pin "1") (pinfunction "1_1") (pintype "passive"))
      (node (ref "C7") (pin "2") (pinfunction "2_2") (pintype "passive"))
      (node (ref "C8") (pin "1") (pinfunction "1_1") (pintype "passive"))
      (node (ref "C9") (pin "1") (pinfunction "1_1") (pintype "passive"))
      (node (ref "IC10") (pin "3") (pinfunction "EN_3") (pintype "bidirectional"))
      (node (ref "IC10") (pin "4") (pinfunction "VIN_4") (pintype "bidirectional"))
      (node (ref "IC15") (pin "10") (pinfunction "VDD_10") (pintype "bidirectional"))
      (node (ref "IC3") (pin "16") (pinfunction "VCC_16") (pintype "power_in"))
      (node (ref "IC5") (pin "10") (pinfunction "EN2_10") (pintype "bidirectional"))
      (node (ref "IC5") (pin "16") (pinfunction "VCC2_16") (pintype "bidirectional"))
      (node (ref "IC6") (pin "10") (pinfunction "VDD_10") (pintype "bidirectional"))
      (node (ref "IC7") (pin "10") (pinfunction "VDD_10") (pintype "bidirectional"))
      (node (ref "IC8") (pin "3") (pinfunction "EN_3") (pintype "bidirectional"))
      (node (ref "IC8") (pin "4") (pinfunction "VIN_4") (pintype "bidirectional"))
      (node (ref "IC9") (pin "3") (pinfunction "EN_3") (pintype "bidirectional"))
      (node (ref "IC9") (pin "4") (pinfunction "VIN_4") (pintype "bidirectional"))
      (node (ref "LED1") (pin "A") (pinfunction "A_A") (pintype "passive"))
      (node (ref "TERA-DC/DC1") (pin "VOUT") (pinfunction "VOUT_VOUT") (pintype "passive"))
      (node (ref "X13") (pin "4") (pinfunction "4_4") (pintype "passive"))
      (node (ref "X14") (pin "4") (pinfunction "4_4") (pintype "passive"))
      (node (ref "X15") (pin "4") (pinfunction "4_4") (pintype "passive"))
      (node (ref "X5") (pin "P$5") (pinfunction "5_P$5") (pintype "bidirectional"))
      (node (ref "X8") (pin "P$9") (pinfunction "9_P$9") (pintype "bidirectional"))
    )
    (net (code "3") (name "+12V") (class "Default")
      (node (ref "C19") (pin "1") (pinfunction "1_1") (pintype "passive"))
      (node (ref "D2") (pin "C") (pinfunction "C_C") (pintype "passive"))
      (node (ref "IC11") (pin "2") (pinfunction "VIN_2") (pintype "passive"))
      (node (ref "LED10") (pin "A") (pinfunction "A_A") (pintype "passive"))
      (node (ref "LED12") (pin "A") (pinfunction "A_A") (pintype "passive"))
      (node (ref "LED13") (pin "A") (pinfunction "A_A") (pintype "passive"))
      (node (ref "LED6") (pin "A") (pinfunction "A_A") (pintype "passive"))
      (node (ref "LED7") (pin "A") (pinfunction "A_A") (pintype "passive"))
      (node (ref "LED8") (pin "A") (pinfunction "A_A") (pintype "passive"))
      (node (ref "LED9") (pin "A") (pinfunction "A_A") (pintype "passive"))
      (node (ref "TB1") (pin "VIN") (pinfunction "VIN_VIN") (pintype "passive"))
      (node (ref "TERA-DC/DC1") (pin "VIN") (pinfunction "VIN_VIN") (pintype "passive"))
      (node (ref "X1") (pin "2") (pinfunction "2_2") (pintype "passive"))
      (node (ref "X10") (pin "P$2") (pinfunction "2_P$2") (pintype "bidirectional"))
      (node (ref "X10") (pin "P$4") (pinfunction "4_P$4") (pintype "bidirectional"))
      (node (ref "X11") (pin "P$2") (pinfunction "2_P$2") (pintype "bidirectional"))
      (node (ref "X12") (pin "P$2") (pinfunction "2_P$2") (pintype "bidirectional"))
      (node (ref "X12") (pin "P$4") (pinfunction "4_P$4") (pintype "bidirectional"))
      (node (ref "X21") (pin "P$2") (pinfunction "2_P$2") (pintype "bidirectional"))
      (node (ref "X21") (pin "P$4") (pinfunction "4_P$4") (pintype "bidirectional"))
      (node (ref "X22") (pin "P$2") (pinfunction "2_P$2") (pintype "bidirectional"))
      (node (ref "X22") (pin "P$4") (pinfunction "4_P$4") (pintype "bidirectional"))
      (node (ref "X3") (pin "4") (pinfunction "V+_4") (pintype "passive"))
      (node (ref "X4") (pin "4") (pinfunction "V+_4") (pintype "passive"))
      (node (ref "X7") (pin "P$2") (pinfunction "2_P$2") (pintype "bidirectional"))
      (node (ref "X9") (pin "P$2") (pinfunction "2_P$2") (pintype "bidirectional"))
    )
    (net (code "4") (name "CAN1_H") (class "Default")
      (node (ref "C27") (pin "2") (pinfunction "2_2") (pintype "passive"))
      (node (ref "D12") (pin "1") (pinfunction "P$1_1") (pintype "passive"))
      (node (ref "L2") (pin "P$3") (pinfunction "3_P$3") (pintype "passive"))
      (node (ref "SW1") (pin "1") (pinfunction "1_1") (pintype "passive"))
      (node (ref "X3") (pin "3") (pinfunction "CANH_3") (pintype "passive"))
    )
    (net (code "5") (name "CAN1_H0") (class "Default")
      (node (ref "D4") (pin "1") (pinfunction "P$1_1") (pintype "passive"))
      (node (ref "IC2") (pin "7") (pinfunction "CANH_7") (pintype "bidirectional"))
      (node (ref "L2") (pin "P$4") (pinfunction "4_P$4") (pintype "passive"))
      (node (ref "SJ1") (pin "1") (pinfunction "1_1") (pintype "passive"))
    )
    (net (code "6") (name "CAN1_L") (class "Default")
      (node (ref "C27") (pin "1") (pinfunction "1_1") (pintype "passive"))
      (node (ref "D12") (pin "2") (pinfunction "P$2_2") (pintype "passive"))
      (node (ref "L2") (pin "P$1") (pinfunction "1_P$1") (pintype "passive"))
      (node (ref "SW1") (pin "2") (pinfunction "2_2") (pintype "passive"))
      (node (ref "X3") (pin "2") (pinfunction "CANL_2") (pintype "passive"))
    )
    (net (code "7") (name "CAN1_L0") (class "Default")
      (node (ref "D4") (pin "2") (pinfunction "P$2_2") (pintype "passive"))
      (node (ref "IC2") (pin "6") (pinfunction "CANL_6") (pintype "bidirectional"))
      (node (ref "L2") (pin "P$2") (pinfunction "2_P$2") (pintype "passive"))
      (node (ref "SJ2") (pin "1") (pinfunction "1_1") (pintype "passive"))
    )
    (net (code "8") (name "CAN1_RXD") (class "Default")
      (node (ref "IC2") (pin "4") (pinfunction "RXD_4") (pintype "output"))
      (node (ref "PROZ1") (pin "26") (pinfunction "PA11_26") (pintype "bidirectional"))
    )
    (net (code "9") (name "CAN1_TXD") (class "Default")
      (node (ref "IC2") (pin "1") (pinfunction "TXD_1") (pintype "input"))
      (node (ref "PROZ1") (pin "24") (pinfunction "PA12_24") (pintype "bidirectional"))
    )
    (net (code "10") (name "CAN2_H") (class "Default")
      (node (ref "C28") (pin "2") (pinfunction "2_2") (pintype "passive"))
      (node (ref "D13") (pin "2") (pinfunction "P$2_2") (pintype "passive"))
      (node (ref "L1") (pin "P$3") (pinfunction "3_P$3") (pintype "passive"))
      (node (ref "SW2") (pin "2") (pinfunction "2_2") (pintype "passive"))
      (node (ref "X4") (pin "3") (pinfunction "CANH_3") (pintype "passive"))
    )
    (net (code "11") (name "CAN2_H0") (class "Default")
      (node (ref "D3") (pin "1") (pinfunction "P$1_1") (pintype "passive"))
      (node (ref "IC1") (pin "7") (pinfunction "CANH_7") (pintype "bidirectional"))
      (node (ref "L1") (pin "P$4") (pinfunction "4_P$4") (pintype "passive"))
    )
    (net (code "12") (name "CAN2_L") (class "Default")
      (node (ref "C28") (pin "1") (pinfunction "1_1") (pintype "passive"))
      (node (ref "D13") (pin "1") (pinfunction "P$1_1") (pintype "passive"))
      (node (ref "L1") (pin "P$1") (pinfunction "1_P$1") (pintype "passive"))
      (node (ref "SW2") (pin "1") (pinfunction "1_1") (pintype "passive"))
      (node (ref "X4") (pin "2") (pinfunction "CANL_2") (pintype "passive"))
    )
    (net (code "13") (name "CAN2_L0") (class "Default")
      (node (ref "D3") (pin "2") (pinfunction "P$2_2") (pintype "passive"))
      (node (ref "IC1") (pin "6") (pinfunction "CANL_6") (pintype "bidirectional"))
      (node (ref "L1") (pin "P$2") (pinfunction "2_P$2") (pintype "passive"))
    )
    (net (code "14") (name "CAN2_RXD") (class "Default")
      (node (ref "IC1") (pin "4") (pinfunction "RXD_4") (pintype "output"))
      (node (ref "PROZ1") (pin "50") (pinfunction "PB12_50") (pintype "bidirectional"))
    )
    (net (code "15") (name "CAN2_TXD") (class "Default")
      (node (ref "IC1") (pin "1") (pinfunction "TXD_1") (pintype "input"))
      (node (ref "PROZ1") (pin "49") (pinfunction "PB13_49") (pintype "bidirectional"))
    )
    (net (code "16") (name "CANP_H") (class "Default")
      (node (ref "PROZ1") (pin "31") (pinfunction "CANH_31") (pintype "bidirectional"))
      (node (ref "SJ1") (pin "2") (pinfunction "2_2") (pintype "passive"))
    )
    (net (code "17") (name "CANP_L") (class "Default")
      (node (ref "PROZ1") (pin "32") (pinfunction "CANL_32") (pintype "bidirectional"))
      (node (ref "SJ2") (pin "2") (pinfunction "2_2") (pintype "passive"))
    )
    (net (code "18") (name "CS_B0") (class "Default")
      (node (ref "IC3") (pin "1") (pinfunction "A_1") (pintype "input"))
      (node (ref "PROZ1") (pin "43") (pinfunction "PA4_43") (pintype "bidirectional"))
    )
    (net (code "19") (name "CS_B1") (class "Default")
      (node (ref "IC3") (pin "2") (pinfunction "B_2") (pintype "input"))
      (node (ref "PROZ1") (pin "51") (pinfunction "PB15_51") (pintype "bidirectional"))
    )
    (net (code "20") (name "CS_B2") (class "Default")
      (node (ref "IC3") (pin "3") (pinfunction "C_3") (pintype "input"))
      (node (ref "PROZ1") (pin "52") (pinfunction "PC6_52") (pintype "bidirectional"))
    )
    (net (code "21") (name "GND") (class "Default")
      (node (ref "C1") (pin "2") (pinfunction "2_2") (pintype "passive"))
      (node (ref "C10") (pin "2") (pinfunction "2_2") (pintype "passive"))
      (node (ref "C11") (pin "2") (pinfunction "2_2") (pintype "passive"))
      (node (ref "C12") (pin "2") (pinfunction "2_2") (pintype "passive"))
      (node (ref "C13") (pin "2") (pinfunction "2_2") (pintype "passive"))
      (node (ref "C14") (pin "2") (pinfunction "2_2") (pintype "passive"))
      (node (ref "C15") (pin "2") (pinfunction "2_2") (pintype "passive"))
      (node (ref "C16") (pin "2") (pinfunction "2_2") (pintype "passive"))
      (node (ref "C17") (pin "2") (pinfunction "2_2") (pintype "passive"))
      (node (ref "C18") (pin "2") (pinfunction "2_2") (pintype "passive"))
      (node (ref "C19") (pin "2") (pinfunction "2_2") (pintype "passive"))
      (node (ref "C2") (pin "2") (pinfunction "2_2") (pintype "passive"))
      (node (ref "C22") (pin "2") (pinfunction "2_2") (pintype "passive"))
      (node (ref "C23") (pin "1") (pinfunction "1_1") (pintype "passive"))
      (node (ref "C24") (pin "2") (pinfunction "2_2") (pintype "passive"))
      (node (ref "C3") (pin "2") (pinfunction "2_2") (pintype "passive"))
      (node (ref "C4") (pin "2") (pinfunction "2_2") (pintype "passive"))
      (node (ref "C5") (pin "2") (pinfunction "2_2") (pintype "passive"))
      (node (ref "C7") (pin "1") (pinfunction "1_1") (pintype "passive"))
      (node (ref "C8") (pin "2") (pinfunction "2_2") (pintype "passive"))
      (node (ref "C9") (pin "2") (pinfunction "2_2") (pintype "passive"))
      (node (ref "D1") (pin "P$1") (pinfunction "P$1_P$1") (pintype "bidirectional"))
      (node (ref "D1") (pin "P$11") (pinfunction "P$1_P$11") (pintype "bidirectional"))
      (node (ref "D10") (pin "P$1") (pinfunction "P$1_P$1") (pintype "bidirectional"))
      (node (ref "D10") (pin "P$11") (pinfunction "P$1_P$11") (pintype "bidirectional"))
      (node (ref "D11") (pin "P$1") (pinfunction "P$1_P$1") (pintype "bidirectional"))
      (node (ref "D11") (pin "P$11") (pinfunction "P$1_P$11") (pintype "bidirectional"))
      (node (ref "D12") (pin "3") (pinfunction "P$3_3") (pintype "passive"))
      (node (ref "D13") (pin "3") (pinfunction "P$3_3") (pintype "passive"))
      (node (ref "D2") (pin "A") (pinfunction "A_A") (pintype "passive"))
      (node (ref "D3") (pin "3") (pinfunction "P$3_3") (pintype "passive"))
      (node (ref "D4") (pin "3") (pinfunction "P$3_3") (pintype "passive"))
      (node (ref "D5") (pin "P$1") (pinfunction "P$1_P$1") (pintype "bidirectional"))
      (node (ref "D5") (pin "P$11") (pinfunction "P$1_P$11") (pintype "bidirectional"))
      (node (ref "D6") (pin "P$1") (pinfunction "P$1_P$1") (pintype "bidirectional"))
      (node (ref "D6") (pin "P$11") (pinfunction "P$1_P$11") (pintype "bidirectional"))
      (node (ref "D7") (pin "P$1") (pinfunction "P$1_P$1") (pintype "bidirectional"))
      (node (ref "D7") (pin "P$11") (pinfunction "P$1_P$11") (pintype "bidirectional"))
      (node (ref "D8") (pin "P$1") (pinfunction "P$1_P$1") (pintype "bidirectional"))
      (node (ref "D8") (pin "P$11") (pinfunction "P$1_P$11") (pintype "bidirectional"))
      (node (ref "D9") (pin "P$1") (pinfunction "P$1_P$1") (pintype "bidirectional"))
      (node (ref "D9") (pin "P$11") (pinfunction "P$1_P$11") (pintype "bidirectional"))
      (node (ref "IC1") (pin "2") (pinfunction "GND_2") (pintype "power_in"))
      (node (ref "IC10") (pin "2") (pinfunction "GND_2") (pintype "bidirectional"))
      (node (ref "IC11") (pin "4") (pinfunction "GND_4") (pintype "power_in"))
      (node (ref "IC15") (pin "12") (pinfunction "GND2_12") (pintype "bidirectional"))
      (node (ref "IC15") (pin "13") (pinfunction "HEAT_13") (pintype "bidirectional"))
      (node (ref "IC15") (pin "6") (pinfunction "GND1_6") (pintype "bidirectional"))
      (node (ref "IC2") (pin "2") (pinfunction "GND_2") (pintype "power_in"))
      (node (ref "IC3") (pin "4") (pinfunction "G2A_4") (pintype "input"))
      (node (ref "IC3") (pin "5") (pinfunction "G2B_5") (pintype "input"))
      (node (ref "IC3") (pin "8") (pinfunction "GND_8") (pintype "power_in"))
      (node (ref "IC5") (pin "15") (pinfunction "GND21_15") (pintype "bidirectional"))
      (node (ref "IC5") (pin "2") (pinfunction "GND11_2") (pintype "bidirectional"))
      (node (ref "IC5") (pin "8") (pinfunction "GND12_8") (pintype "bidirectional"))
      (node (ref "IC5") (pin "9") (pinfunction "GND22_9") (pintype "bidirectional"))
      (node (ref "IC6") (pin "12") (pinfunction "GND2_12") (pintype "bidirectional"))
      (node (ref "IC6") (pin "13") (pinfunction "HEAT_13") (pintype "bidirectional"))
      (node (ref "IC6") (pin "6") (pinfunction "GND1_6") (pintype "bidirectional"))
      (node (ref "IC7") (pin "12") (pinfunction "GND2_12") (pintype "bidirectional"))
      (node (ref "IC7") (pin "13") (pinfunction "HEAT_13") (pintype "bidirectional"))
      (node (ref "IC7") (pin "6") (pinfunction "GND1_6") (pintype "bidirectional"))
      (node (ref "IC8") (pin "2") (pinfunction "GND_2") (pintype "bidirectional"))
      (node (ref "IC9") (pin "2") (pinfunction "GND_2") (pintype "bidirectional"))
      (node (ref "PROZ1") (pin "47") (pinfunction "GND_47") (pintype "passive"))
      (node (ref "PROZ1") (pin "48") (pinfunction "GND_48") (pintype "passive"))
      (node (ref "Q12") (pin "2") (pinfunction "S_2") (pintype "passive"))
      (node (ref "Q13") (pin "2") (pinfunction "S_2") (pintype "passive"))
      (node (ref "Q3") (pin "2") (pinfunction "S_2") (pintype "passive"))
      (node (ref "Q4") (pin "2") (pinfunction "S_2") (pintype "passive"))
      (node (ref "R1") (pin "1") (pinfunction "1_1") (pintype "passive"))
      (node (ref "R10") (pin "1") (pinfunction "1_1") (pintype "passive"))
      (node (ref "R11") (pin "1") (pinfunction "1_1") (pintype "passive"))
      (node (ref "R2") (pin "1") (pinfunction "1_1") (pintype "passive"))
      (node (ref "R20") (pin "1") (pinfunction "1_1") (pintype "passive"))
      (node (ref "R23") (pin "1") (pinfunction "1_1") (pintype "passive"))
      (node (ref "R27") (pin "2") (pinfunction "2_2") (pintype "passive"))
      (node (ref "R29") (pin "2") (pinfunction "2_2") (pintype "passive"))
      (node (ref "R3") (pin "1") (pinfunction "1_1") (pintype "passive"))
      (node (ref "R32") (pin "2") (pinfunction "2_2") (pintype "passive"))
      (node (ref "R34") (pin "2") (pinfunction "2_2") (pintype "passive"))
      (node (ref "R4") (pin "1") (pinfunction "1_1") (pintype "passive"))
      (node (ref "R56") (pin "2") (pinfunction "2_2") (pintype "passive"))
      (node (ref "R57") (pin "2") (pinfunction "2_2") (pintype "passive"))
      (node (ref "R58") (pin "2") (pinfunction "2_2") (pintype "passive"))
      (node (ref "R63") (pin "1") (pinfunction "1_1") (pintype "passive"))
      (node (ref "R77") (pin "1") (pinfunction "1_1") (pintype "passive"))
      (node (ref "R78") (pin "1") (pinfunction "1_1") (pintype "passive"))
      (node (ref "R9") (pin "1") (pinfunction "1_1") (pintype "passive"))
      (node (ref "TB1") (pin "GND") (pinfunction "GND_GND") (pintype "power_in"))
      (node (ref "TB1") (pin "GND2") (pinfunction "GND_GND2") (pintype "power_in"))
      (node (ref "TERA-DC/DC1") (pin "GND@1") (pinfunction "GND_GND@1") (pintype "power_in"))
      (node (ref "TERA-DC/DC1") (pin "GND@2") (pinfunction "GND_GND@2") (pintype "power_in"))
      (node (ref "X1") (pin "1") (pinfunction "1_1") (pintype "passive"))
      (node (ref "X13") (pin "1") (pinfunction "1_1") (pintype "passive"))
      (node (ref "X14") (pin "1") (pinfunction "1_1") (pintype "passive"))
      (node (ref "X15") (pin "1") (pinfunction "1_1") (pintype "passive"))
      (node (ref "X2") (pin "1") (pinfunction "GND_1") (pintype "passive"))
      (node (ref "X3") (pin "1") (pinfunction "GND_1") (pintype "passive"))
      (node (ref "X4") (pin "1") (pinfunction "GND_1") (pintype "passive"))
      (node (ref "X5") (pin "P$1") (pinfunction "1_P$1") (pintype "bidirectional"))
      (node (ref "X7") (pin "P$1") (pinfunction "1_P$1") (pintype "bidirectional"))
      (node (ref "X8") (pin "P$1") (pinfunction "1_P$1") (pintype "bidirectional"))
    )
    (net (code "22") (name "HS_CO1") (class "Default")
      (node (ref "IC7") (pin "4") (pinfunction "CO1_4") (pintype "bidirectional"))
      (node (ref "PROZ1") (pin "36") (pinfunction "PB2_36") (pintype "bidirectional"))
    )
    (net (code "23") (name "HS_RM") (class "Default")
      (node (ref "PROZ1") (pin "37") (pinfunction "PB1_37") (pintype "bidirectional"))
      (node (ref "Q4") (pin "3") (pinfunction "D_3") (pintype "passive"))
      (node (ref "R21") (pin "1") (pinfunction "1_1") (pintype "passive"))
    )
    (net (code "24") (name "HS_RM_EX") (class "Default")
      (node (ref "R22") (pin "2") (pinfunction "2_2") (pintype "passive"))
      (node (ref "X11") (pin "P$3") (pinfunction "3_P$3") (pintype "bidirectional"))
    )
    (net (code "25") (name "IL1") (class "Default")
      (node (ref "PROZ1") (pin "14") (pinfunction "PB6_14") (pintype "bidirectional"))
      (node (ref "X5") (pin "P$3") (pinfunction "3_P$3") (pintype "bidirectional"))
    )
    (net (code "26") (name "IL2") (class "Default")
      (node (ref "PROZ1") (pin "12") (pinfunction "PB7_12") (pintype "bidirectional"))
      (node (ref "X5") (pin "P$2") (pinfunction "2_P$2") (pintype "bidirectional"))
    )
    (net (code "27") (name "INTERLOCK_OK") (class "Default")
      (node (ref "IC15") (pin "1") (pinfunction "IN2_1") (pintype "bidirectional"))
      (node (ref "IC15") (pin "7") (pinfunction "IN1_7") (pintype "bidirectional"))
      (node (ref "IC6") (pin "1") (pinfunction "IN2_1") (pintype "bidirectional"))
      (node (ref "IC6") (pin "7") (pinfunction "IN1_7") (pintype "bidirectional"))
      (node (ref "IC7") (pin "1") (pinfunction "IN2_1") (pintype "bidirectional"))
      (node (ref "IC7") (pin "7") (pinfunction "IN1_7") (pintype "bidirectional"))
      (node (ref "PROZ1") (pin "44") (pinfunction "PA3_44") (pintype "bidirectional"))
      (node (ref "R9") (pin "2") (pinfunction "2_2") (pintype "passive"))
      (node (ref "X5") (pin "P$4") (pinfunction "4_P$4") (pintype "bidirectional"))
    )
    (net (code "28") (name "JTCK") (class "Default")
      (node (ref "PROZ1") (pin "18") (pinfunction "PA14_18") (pintype "bidirectional"))
      (node (ref "X2") (pin "5") (pinfunction "JTCK_5") (pintype "passive"))
    )
    (net (code "29") (name "JTDI") (class "Default")
      (node (ref "PROZ1") (pin "16") (pinfunction "PA15_16") (pintype "bidirectional"))
      (node (ref "X2") (pin "6") (pinfunction "JTDI_6") (pintype "passive"))
    )
    (net (code "30") (name "JTDO") (class "Default")
      (node (ref "PROZ1") (pin "20") (pinfunction "PB3_20") (pintype "bidirectional"))
      (node (ref "X2") (pin "7") (pinfunction "JTDO_7") (pintype "passive"))
    )
    (net (code "31") (name "JTMS") (class "Default")
      (node (ref "PROZ1") (pin "59") (pinfunction "PA13_59") (pintype "bidirectional"))
      (node (ref "X2") (pin "3") (pinfunction "JTMS_3") (pintype "passive"))
    )
    (net (code "32") (name "JTNRST") (class "Default")
      (node (ref "PROZ1") (pin "22") (pinfunction "PB4_22") (pintype "bidirectional"))
      (node (ref "X2") (pin "8") (pinfunction "JTNRST_8") (pintype "passive"))
    )
    (net (code "33") (name "LED1") (class "Default")
      (node (ref "PROZ1") (pin "25") (pinfunction "PB5_25") (pintype "bidirectional"))
    )
    (net (code "34") (name "LED2") (class "Default")
      (node (ref "PROZ1") (pin "27") (pinfunction "PD2_27") (pintype "bidirectional"))
    )
    (net (code "35") (name "LED3") (class "Default")
      (node (ref "PROZ1") (pin "29") (pinfunction "PC12_29") (pintype "bidirectional"))
    )
    (net (code "36") (name "LEM_1") (class "Default")
      (node (ref "C18") (pin "1") (pinfunction "1_1") (pintype "passive"))
      (node (ref "D7") (pin "P$2") (pinfunction "P$2_P$2") (pintype "bidirectional"))
      (node (ref "PROZ1") (pin "15") (pinfunction "PC0_15") (pintype "bidirectional"))
      (node (ref "R26") (pin "2") (pinfunction "2_2") (pintype "passive"))
    )
    (net (code "37") (name "LEM_2") (class "Default")
      (node (ref "C17") (pin "1") (pinfunction "1_1") (pintype "passive"))
      (node (ref "D6") (pin "P$2") (pinfunction "P$2_P$2") (pintype "bidirectional"))
      (node (ref "PROZ1") (pin "13") (pinfunction "PC1_13") (pintype "bidirectional"))
      (node (ref "R25") (pin "2") (pinfunction "2_2") (pintype "passive"))
    )
    (net (code "38") (name "LEM_3") (class "Default")
      (node (ref "C16") (pin "1") (pinfunction "1_1") (pintype "passive"))
      (node (ref "D8") (pin "P$2") (pinfunction "P$2_P$2") (pintype "bidirectional"))
      (node (ref "PROZ1") (pin "11") (pinfunction "PC2_11") (pintype "bidirectional"))
      (node (ref "R24") (pin "2") (pinfunction "2_2") (pintype "passive"))
    )
    (net (code "39") (name "MISO") (class "Default")
      (node (ref "IC15") (pin "11") (pinfunction "MISO/ST2_11") (pintype "bidirectional"))
      (node (ref "IC5") (pin "11") (pinfunction "IN_D_11") (pintype "bidirectional"))
      (node (ref "IC6") (pin "11") (pinfunction "MISO/ST2_11") (pintype "bidirectional"))
      (node (ref "IC7") (pin "11") (pinfunction "MISO/ST2_11") (pintype "bidirectional"))
      (node (ref "X8") (pin "P$7") (pinfunction "7_P$7") (pintype "bidirectional"))
    )
    (net (code "40") (name "MISO_M") (class "Default")
      (node (ref "IC5") (pin "6") (pinfunction "OUT_D_6") (pintype "bidirectional"))
      (node (ref "PROZ1") (pin "42") (pinfunction "PA6_42") (pintype "bidirectional"))
    )
    (net (code "41") (name "MOSI") (class "Default")
      (node (ref "IC15") (pin "2") (pinfunction "MOSI_2") (pintype "bidirectional"))
      (node (ref "IC5") (pin "13") (pinfunction "OUT_B_13") (pintype "bidirectional"))
      (node (ref "IC6") (pin "2") (pinfunction "MOSI_2") (pintype "bidirectional"))
      (node (ref "IC7") (pin "2") (pinfunction "MOSI_2") (pintype "bidirectional"))
      (node (ref "X8") (pin "P$6") (pinfunction "6_P$6") (pintype "bidirectional"))
    )
    (net (code "42") (name "MOSI_M") (class "Default")
      (node (ref "IC5") (pin "4") (pinfunction "IN_B_4") (pintype "bidirectional"))
      (node (ref "PROZ1") (pin "41") (pinfunction "PA7_41") (pintype "bidirectional"))
    )
    (net (code "43") (name "NALERT") (class "Default")
      (node (ref "PROZ1") (pin "35") (pinfunction "PB10_35") (pintype "bidirectional"))
      (node (ref "R11") (pin "2") (pinfunction "2_2") (pintype "passive"))
      (node (ref "X6") (pin "P$2") (pinfunction "2_P$2") (pintype "bidirectional"))
    )
    (net (code "44") (name "NCS1") (class "Default")
      (node (ref "IC3") (pin "15") (pinfunction "Y0_15") (pintype "output"))
      (node (ref "X8") (pin "P$5") (pinfunction "5_P$5") (pintype "bidirectional"))
    )
    (net (code "45") (name "NCS2") (class "Default")
      (node (ref "IC3") (pin "14") (pinfunction "Y1_14") (pintype "output"))
      (node (ref "X8") (pin "P$4") (pinfunction "4_P$4") (pintype "bidirectional"))
    )
    (net (code "46") (name "NCS3") (class "Default")
      (node (ref "IC3") (pin "13") (pinfunction "Y2_13") (pintype "output"))
      (node (ref "X8") (pin "P$3") (pinfunction "3_P$3") (pintype "bidirectional"))
    )
    (net (code "47") (name "NCS4") (class "Default")
      (node (ref "IC3") (pin "12") (pinfunction "Y3_12") (pintype "output"))
      (node (ref "X8") (pin "P$2") (pinfunction "2_P$2") (pintype "bidirectional"))
    )
    (net (code "48") (name "NCS5") (class "Default")
      (node (ref "IC3") (pin "11") (pinfunction "Y4_11") (pintype "output"))
    )
    (net (code "49") (name "NCS6") (class "Default")
      (node (ref "IC3") (pin "10") (pinfunction "Y5_10") (pintype "output"))
      (node (ref "IC7") (pin "8") (pinfunction "NCS_8") (pintype "bidirectional"))
    )
    (net (code "50") (name "NCS7") (class "Default")
      (node (ref "IC3") (pin "9") (pinfunction "Y6_9") (pintype "output"))
      (node (ref "IC6") (pin "8") (pinfunction "NCS_8") (pintype "bidirectional"))
    )
    (net (code "51") (name "NCS8") (class "Default")
      (node (ref "IC15") (pin "8") (pinfunction "NCS_8") (pintype "bidirectional"))
      (node (ref "IC3") (pin "7") (pinfunction "Y7_7") (pintype "output"))
    )
    (net (code "52") (name "NFAULT") (class "Default")
      (node (ref "PROZ1") (pin "53") (pinfunction "PC7_53") (pintype "bidirectional"))
      (node (ref "R10") (pin "2") (pinfunction "2_2") (pintype "passive"))
      (node (ref "X6") (pin "P$1") (pinfunction "1_P$1") (pintype "bidirectional"))
    )
    (net (code "53") (name "NRST") (class "Default")
      (node (ref "PROZ1") (pin "17") (pinfunction "NRST_17") (pintype "bidirectional"))
      (node (ref "X2") (pin "4") (pinfunction "NRST_4") (pintype "passive"))
    )
    (net (code "54") (name "Net-(C4-Pad1)") (class "Default")
      (node (ref "C4") (pin "1") (pinfunction "1_1") (pintype "passive"))
      (node (ref "R5") (pin "1") (pinfunction "1_1") (pintype "passive"))
      (node (ref "R6") (pin "1") (pinfunction "1_1") (pintype "passive"))
    )
    (net (code "55") (name "Net-(C5-Pad1)") (class "Default")
      (node (ref "C5") (pin "1") (pinfunction "1_1") (pintype "passive"))
      (node (ref "R7") (pin "1") (pinfunction "1_1") (pintype "passive"))
      (node (ref "R8") (pin "1") (pinfunction "1_1") (pintype "passive"))
    )
    (net (code "56") (name "Net-(CON2-Pad1)") (class "Default")
      (node (ref "CON2") (pin "1") (pinfunction "1_1") (pintype "passive"))
      (node (ref "R30") (pin "1") (pinfunction "1_1") (pintype "passive"))
    )
    (net (code "57") (name "Net-(CON3-Pad1)") (class "Default")
      (node (ref "CON3") (pin "1") (pinfunction "1_1") (pintype "passive"))
      (node (ref "R28") (pin "1") (pinfunction "1_1") (pintype "passive"))
    )
    (net (code "58") (name "Net-(CON4-Pad1)") (class "Default")
      (node (ref "CON4") (pin "1") (pinfunction "1_1") (pintype "passive"))
      (node (ref "R31") (pin "1") (pinfunction "1_1") (pintype "passive"))
    )
    (net (code "59") (name "Net-(CON5-Pad1)") (class "Default")
      (node (ref "CON5") (pin "1") (pinfunction "1_1") (pintype "passive"))
      (node (ref "R33") (pin "1") (pinfunction "1_1") (pintype "passive"))
    )
    (net (code "60") (name "Net-(IC1-RS)") (class "Default")
      (node (ref "IC1") (pin "8") (pinfunction "RS_8") (pintype "passive"))
      (node (ref "R3") (pin "2") (pinfunction "2_2") (pintype "passive"))
    )
    (net (code "61") (name "Net-(IC2-RS)") (class "Default")
      (node (ref "IC2") (pin "8") (pinfunction "RS_8") (pintype "passive"))
      (node (ref "R4") (pin "2") (pinfunction "2_2") (pintype "passive"))
    )
    (net (code "62") (name "Net-(IC2-VCC)") (class "Default")
      (node (ref "C2") (pin "1") (pinfunction "1_1") (pintype "passive"))
      (node (ref "IC2") (pin "3") (pinfunction "VCC_3") (pintype "power_in"))
      (node (ref "J3") (pin "P$2") (pinfunction "P$2_P$2") (pintype "bidirectional"))
    )
    (net (code "63") (name "Net-(IC6-OUT1)") (class "Default")
      (node (ref "IC6") (pin "9") (pinfunction "OUT1_9") (pintype "bidirectional"))
      (node (ref "R61") (pin "1") (pinfunction "1_1") (pintype "passive"))
      (node (ref "X10") (pin "P$1") (pinfunction "1_P$1") (pintype "bidirectional"))
    )
    (net (code "64") (name "Net-(IC6-OUT2)") (class "Default")
      (node (ref "IC6") (pin "3") (pinfunction "OUT2_3") (pintype "bidirectional"))
      (node (ref "R62") (pin "1") (pinfunction "1_1") (pintype "passive"))
      (node (ref "X9") (pin "P$1") (pinfunction "1_P$1") (pintype "bidirectional"))
    )
    (net (code "65") (name "Net-(IC7-OUT1)") (class "Default")
      (node (ref "IC7") (pin "9") (pinfunction "OUT1_9") (pintype "bidirectional"))
      (node (ref "R59") (pin "1") (pinfunction "1_1") (pintype "passive"))
      (node (ref "X12") (pin "P$1") (pinfunction "1_P$1") (pintype "bidirectional"))
    )
    (net (code "66") (name "Net-(IC7-OUT2)") (class "Default")
      (node (ref "IC7") (pin "3") (pinfunction "OUT2_3") (pintype "bidirectional"))
      (node (ref "R60") (pin "1") (pinfunction "1_1") (pintype "passive"))
      (node (ref "X11") (pin "P$1") (pinfunction "1_P$1") (pintype "bidirectional"))
    )
    (net (code "67") (name "Net-(IC8-VREF)") (class "Default")
      (node (ref "C13") (pin "1") (pinfunction "1_1") (pintype "passive"))
      (node (ref "IC8") (pin "5") (pinfunction "VREF_5") (pintype "bidirectional"))
      (node (ref "R58") (pin "1") (pinfunction "1_1") (pintype "passive"))
      (node (ref "X13") (pin "3") (pinfunction "3_3") (pintype "passive"))
    )
    (net (code "68") (name "Net-(IC9-VREF)") (class "Default")
      (node (ref "C14") (pin "1") (pinfunction "1_1") (pintype "passive"))
      (node (ref "IC9") (pin "5") (pinfunction "VREF_5") (pintype "bidirectional"))
      (node (ref "R57") (pin "1") (pinfunction "1_1") (pintype "passive"))
      (node (ref "X14") (pin "3") (pinfunction "3_3") (pintype "passive"))
    )
    (net (code "69") (name "Net-(IC10-VREF)") (class "Default")
      (node (ref "C15") (pin "1") (pinfunction "1_1") (pintype "passive"))
      (node (ref "IC10") (pin "5") (pinfunction "VREF_5") (pintype "bidirectional"))
      (node (ref "R56") (pin "1") (pinfunction "1_1") (pintype "passive"))
      (node (ref "X15") (pin "3") (pinfunction "3_3") (pintype "passive"))
    )
    (net (code "70") (name "Net-(IC15-OUT1)") (class "Default")
      (node (ref "IC15") (pin "9") (pinfunction "OUT1_9") (pintype "bidirectional"))
      (node (ref "R71") (pin "1") (pinfunction "1_1") (pintype "passive"))
      (node (ref "X21") (pin "P$1") (pinfunction "1_P$1") (pintype "bidirectional"))
    )
    (net (code "71") (name "Net-(IC15-OUT2)") (class "Default")
      (node (ref "IC15") (pin "3") (pinfunction "OUT2_3") (pintype "bidirectional"))
      (node (ref "R72") (pin "1") (pinfunction "1_1") (pintype "passive"))
      (node (ref "X22") (pin "P$1") (pinfunction "1_P$1") (pintype "bidirectional"))
    )
    (net (code "72") (name "Net-(LED1-PadC)") (class "Default")
      (node (ref "LED1") (pin "C") (pinfunction "C_C") (pintype "passive"))
      (node (ref "R1") (pin "2") (pinfunction "2_2") (pintype "passive"))
    )
    (net (code "73") (name "Net-(LED2-PadC)") (class "Default")
      (node (ref "LED2") (pin "C") (pinfunction "C_C") (pintype "passive"))
      (node (ref "R2") (pin "2") (pinfunction "2_2") (pintype "passive"))
    )
    (net (code "74") (name "Net-(LED6-PadC)") (class "Default")
      (node (ref "LED6") (pin "C") (pinfunction "C_C") (pintype "passive"))
      (node (ref "R59") (pin "2") (pinfunction "2_2") (pintype "passive"))
    )
    (net (code "75") (name "Net-(LED7-PadC)") (class "Default")
      (node (ref "LED7") (pin "C") (pinfunction "C_C") (pintype "passive"))
      (node (ref "R60") (pin "2") (pinfunction "2_2") (pintype "passive"))
    )
    (net (code "76") (name "Net-(LED8-PadC)") (class "Default")
      (node (ref "LED8") (pin "C") (pinfunction "C_C") (pintype "passive"))
      (node (ref "R61") (pin "2") (pinfunction "2_2") (pintype "passive"))
    )
    (net (code "77") (name "Net-(LED9-PadC)") (class "Default")
      (node (ref "LED9") (pin "C") (pinfunction "C_C") (pintype "passive"))
      (node (ref "R62") (pin "2") (pinfunction "2_2") (pintype "passive"))
    )
    (net (code "78") (name "Net-(LED10-PadC)") (class "Default")
      (node (ref "LED10") (pin "C") (pinfunction "C_C") (pintype "passive"))
      (node (ref "R63") (pin "2") (pinfunction "2_2") (pintype "passive"))
    )
    (net (code "79") (name "Net-(LED12-PadC)") (class "Default")
      (node (ref "LED12") (pin "C") (pinfunction "C_C") (pintype "passive"))
      (node (ref "R71") (pin "2") (pinfunction "2_2") (pintype "passive"))
    )
    (net (code "80") (name "Net-(LED13-PadC)") (class "Default")
      (node (ref "LED13") (pin "C") (pinfunction "C_C") (pintype "passive"))
      (node (ref "R72") (pin "2") (pinfunction "2_2") (pintype "passive"))
    )
    (net (code "81") (name "Net-(Q3-G)") (class "Default")
      (node (ref "Q3") (pin "1") (pinfunction "G_1") (pintype "passive"))
      (node (ref "R19") (pin "1") (pinfunction "1_1") (pintype "passive"))
      (node (ref "R20") (pin "2") (pinfunction "2_2") (pintype "passive"))
    )
    (net (code "82") (name "Net-(Q4-G)") (class "Default")
      (node (ref "Q4") (pin "1") (pinfunction "G_1") (pintype "passive"))
      (node (ref "R22") (pin "1") (pinfunction "1_1") (pintype "passive"))
      (node (ref "R23") (pin "2") (pinfunction "2_2") (pintype "passive"))
    )
    (net (code "83") (name "Net-(Q12-G)") (class "Default")
      (node (ref "Q12") (pin "1") (pinfunction "G_1") (pintype "passive"))
      (node (ref "R76") (pin "1") (pinfunction "1_1") (pintype "passive"))
      (node (ref "R78") (pin "2") (pinfunction "2_2") (pintype "passive"))
    )
    (net (code "84") (name "Net-(Q13-G)") (class "Default")
      (node (ref "Q13") (pin "1") (pinfunction "G_1") (pintype "passive"))
      (node (ref "R74") (pin "1") (pinfunction "1_1") (pintype "passive"))
      (node (ref "R77") (pin "2") (pinfunction "2_2") (pintype "passive"))
    )
    (net (code "85") (name "Net-(R5-Pad2)") (class "Default")
      (node (ref "R5") (pin "2") (pinfunction "2_2") (pintype "passive"))
      (node (ref "SW2") (pin "3") (pinfunction "3_3") (pintype "passive"))
    )
    (net (code "86") (name "Net-(R6-Pad2)") (class "Default")
      (node (ref "R6") (pin "2") (pinfunction "2_2") (pintype "passive"))
      (node (ref "SW2") (pin "4") (pinfunction "4_4") (pintype "passive"))
    )
    (net (code "87") (name "Net-(R7-Pad2)") (class "Default")
      (node (ref "R7") (pin "2") (pinfunction "2_2") (pintype "passive"))
      (node (ref "SW1") (pin "4") (pinfunction "4_4") (pintype "passive"))
    )
    (net (code "88") (name "Net-(R8-Pad2)") (class "Default")
      (node (ref "R8") (pin "2") (pinfunction "2_2") (pintype "passive"))
      (node (ref "SW1") (pin "3") (pinfunction "3_3") (pintype "passive"))
    )
    (net (code "89") (name "Net-(R24-Pad1)") (class "Default")
      (node (ref "R24") (pin "1") (pinfunction "1_1") (pintype "passive"))
      (node (ref "X13") (pin "2") (pinfunction "2_2") (pintype "passive"))
    )
    (net (code "90") (name "Net-(R25-Pad1)") (class "Default")
      (node (ref "R25") (pin "1") (pinfunction "1_1") (pintype "passive"))
      (node (ref "X14") (pin "2") (pinfunction "2_2") (pintype "passive"))
    )
    (net (code "91") (name "Net-(R26-Pad1)") (class "Default")
      (node (ref "R26") (pin "1") (pinfunction "1_1") (pintype "passive"))
      (node (ref "X15") (pin "2") (pinfunction "2_2") (pintype "passive"))
    )
    (net (code "92") (name "Net-(X10-3)") (class "Default")
      (node (ref "X10") (pin "P$3") (pinfunction "3_P$3") (pintype "bidirectional"))
      (node (ref "X9") (pin "P$4") (pinfunction "4_P$4") (pintype "bidirectional"))
    )
    (net (code "93") (name "Net-(X11-4)") (class "Default")
      (node (ref "X11") (pin "P$4") (pinfunction "4_P$4") (pintype "bidirectional"))
      (node (ref "X12") (pin "P$3") (pinfunction "3_P$3") (pintype "bidirectional"))
    )
    (net (code "94") (name "PA0") (class "Default")
      (node (ref "PROZ1") (pin "7") (pinfunction "PA0_7") (pintype "bidirectional"))
    )
    (net (code "95") (name "PA10") (class "Default")
      (node (ref "PROZ1") (pin "58") (pinfunction "PA10_58") (pintype "bidirectional"))
    )
    (net (code "96") (name "PB8") (class "Default")
      (node (ref "PROZ1") (pin "10") (pinfunction "PB8_10") (pintype "bidirectional"))
    )
    (net (code "97") (name "PB9") (class "Default")
      (node (ref "PROZ1") (pin "8") (pinfunction "PB9_8") (pintype "bidirectional"))
    )
    (net (code "98") (name "PC3") (class "Default")
      (node (ref "PROZ1") (pin "9") (pinfunction "PC3_9") (pintype "bidirectional"))
    )
    (net (code "99") (name "PC9") (class "Default")
      (node (ref "PROZ1") (pin "55") (pinfunction "PC9_55") (pintype "bidirectional"))
    )
    (net (code "100") (name "PC13") (class "Default")
      (node (ref "PROZ1") (pin "23") (pinfunction "PC13_23") (pintype "bidirectional"))
    )
    (net (code "101") (name "PC14") (class "Default")
      (node (ref "PROZ1") (pin "21") (pinfunction "PC14_21") (pintype "bidirectional"))
    )
    (net (code "102") (name "PC15") (class "Default")
      (node (ref "PROZ1") (pin "19") (pinfunction "PC15_19") (pintype "bidirectional"))
    )
    (net (code "103") (name "RM_KVL1") (class "Default")
      (node (ref "PROZ1") (pin "33") (pinfunction "PB14_33") (pintype "bidirectional"))
      (node (ref "Q13") (pin "3") (pinfunction "D_3") (pintype "passive"))
      (node (ref "R73") (pin "1") (pinfunction "1_1") (pintype "passive"))
    )
    (net (code "104") (name "RM_KVL1_EX") (class "Default")
      (node (ref "R74") (pin "2") (pinfunction "2_2") (pintype "passive"))
      (node (ref "X21") (pin "P$3") (pinfunction "3_P$3") (pintype "bidirectional"))
    )
    (net (code "105") (name "RM_KVL2") (class "Default")
      (node (ref "PROZ1") (pin "34") (pinfunction "PB11_34") (pintype "bidirectional"))
      (node (ref "Q12") (pin "3") (pinfunction "D_3") (pintype "passive"))
      (node (ref "R75") (pin "1") (pinfunction "1_1") (pintype "passive"))
    )
    (net (code "106") (name "RM_KVL2_EX") (class "Default")
      (node (ref "R76") (pin "2") (pinfunction "2_2") (pintype "passive"))
      (node (ref "X22") (pin "P$3") (pinfunction "3_P$3") (pintype "bidirectional"))
    )
    (net (code "107") (name "SCLK") (class "Default")
      (node (ref "IC15") (pin "5") (pinfunction "SCLK_5") (pintype "bidirectional"))
      (node (ref "IC5") (pin "14") (pinfunction "OUT_A_14") (pintype "bidirectional"))
      (node (ref "IC6") (pin "5") (pinfunction "SCLK_5") (pintype "bidirectional"))
      (node (ref "IC7") (pin "5") (pinfunction "SCLK_5") (pintype "bidirectional"))
      (node (ref "X8") (pin "P$8") (pinfunction "8_P$8") (pintype "bidirectional"))
    )
    (net (code "108") (name "SCLK_M") (class "Default")
      (node (ref "IC5") (pin "3") (pinfunction "IN_A_3") (pintype "bidirectional"))
      (node (ref "PROZ1") (pin "60") (pinfunction "PA5_60") (pintype "bidirectional"))
    )
    (net (code "109") (name "SLS_CO1") (class "Default")
      (node (ref "IC6") (pin "4") (pinfunction "CO1_4") (pintype "bidirectional"))
      (node (ref "PROZ1") (pin "57") (pinfunction "PA9_57") (pintype "bidirectional"))
    )
    (net (code "110") (name "SLS_RM") (class "Default")
      (node (ref "PROZ1") (pin "56") (pinfunction "PA8_56") (pintype "bidirectional"))
      (node (ref "Q3") (pin "3") (pinfunction "D_3") (pintype "passive"))
      (node (ref "R18") (pin "1") (pinfunction "1_1") (pintype "passive"))
    )
    (net (code "111") (name "SLS_RM_EX") (class "Default")
      (node (ref "R19") (pin "2") (pinfunction "2_2") (pintype "passive"))
      (node (ref "X9") (pin "P$3") (pinfunction "3_P$3") (pintype "bidirectional"))
    )
    (net (code "112") (name "SPI_CS") (class "Default")
      (node (ref "IC3") (pin "6") (pinfunction "G1_6") (pintype "input"))
      (node (ref "PROZ1") (pin "38") (pinfunction "PB0_38") (pintype "bidirectional"))
    )
    (net (code "113") (name "TS1") (class "Default")
      (node (ref "C21") (pin "2") (pinfunction "2_2") (pintype "passive"))
      (node (ref "D9") (pin "P$2") (pinfunction "P$2_P$2") (pintype "bidirectional"))
      (node (ref "PROZ1") (pin "40") (pinfunction "PC4_40") (pintype "bidirectional"))
      (node (ref "R29") (pin "1") (pinfunction "1_1") (pintype "passive"))
      (node (ref "R30") (pin "2") (pinfunction "2_2") (pintype "passive"))
    )
    (net (code "114") (name "TS2") (class "Default")
      (node (ref "C20") (pin "2") (pinfunction "2_2") (pintype "passive"))
      (node (ref "D10") (pin "P$2") (pinfunction "P$2_P$2") (pintype "bidirectional"))
      (node (ref "PROZ1") (pin "39") (pinfunction "PC5_39") (pintype "bidirectional"))
      (node (ref "R27") (pin "1") (pinfunction "1_1") (pintype "passive"))
      (node (ref "R28") (pin "2") (pinfunction "2_2") (pintype "passive"))
    )
    (net (code "115") (name "TS3") (class "Default")
      (node (ref "C25") (pin "2") (pinfunction "2_2") (pintype "passive"))
      (node (ref "D1") (pin "P$2") (pinfunction "P$2_P$2") (pintype "bidirectional"))
      (node (ref "PROZ1") (pin "5") (pinfunction "PA1_5") (pintype "bidirectional"))
      (node (ref "R31") (pin "2") (pinfunction "2_2") (pintype "passive"))
      (node (ref "R32") (pin "1") (pinfunction "1_1") (pintype "passive"))
    )
    (net (code "116") (name "TS4") (class "Default")
      (node (ref "C26") (pin "2") (pinfunction "2_2") (pintype "passive"))
      (node (ref "D11") (pin "P$2") (pinfunction "P$2_P$2") (pintype "bidirectional"))
      (node (ref "PROZ1") (pin "3") (pinfunction "PA2_3") (pintype "bidirectional"))
      (node (ref "R33") (pin "2") (pinfunction "2_2") (pintype "passive"))
      (node (ref "R34") (pin "1") (pinfunction "1_1") (pintype "passive"))
    )
    (net (code "117") (name "USART_RXD") (class "Default")
      (node (ref "PROZ1") (pin "30") (pinfunction "PC11_30") (pintype "bidirectional"))
      (node (ref "X2") (pin "10") (pinfunction "RXD_10") (pintype "passive"))
    )
    (net (code "118") (name "USART_TXD") (class "Default")
      (node (ref "PROZ1") (pin "28") (pinfunction "PC10_28") (pintype "bidirectional"))
      (node (ref "X2") (pin "9") (pinfunction "TXD_9") (pintype "passive"))
    )
    (net (code "119") (name "VL_CO1") (class "Default")
      (node (ref "IC15") (pin "4") (pinfunction "CO1_4") (pintype "bidirectional"))
      (node (ref "PROZ1") (pin "54") (pinfunction "PC8_54") (pintype "bidirectional"))
    )
    (net (code "120") (name "VREF_PTC_CH") (class "Default")
      (node (ref "C20") (pin "1") (pinfunction "1_1") (pintype "passive"))
      (node (ref "C21") (pin "1") (pinfunction "1_1") (pintype "passive"))
      (node (ref "C22") (pin "1") (pinfunction "1_1") (pintype "passive"))
      (node (ref "C25") (pin "1") (pinfunction "1_1") (pintype "passive"))
      (node (ref "C26") (pin "1") (pinfunction "1_1") (pintype "passive"))
      (node (ref "CON2") (pin "2") (pinfunction "2_2") (pintype "passive"))
      (node (ref "CON3") (pin "2") (pinfunction "2_2") (pintype "passive"))
      (node (ref "CON4") (pin "2") (pinfunction "2_2") (pintype "passive"))
      (node (ref "CON5") (pin "2") (pinfunction "2_2") (pintype "passive"))
      (node (ref "IC11") (pin "6") (pinfunction "VOUT_6") (pintype "bidirectional"))
    )
    (net (code "121") (name "unconnected-(IC1-VREF-Pad5)") (class "Default")
      (node (ref "IC1") (pin "5") (pinfunction "VREF_5") (pintype "passive"))
    )
    (net (code "122") (name "unconnected-(IC2-VREF-Pad5)") (class "Default")
      (node (ref "IC2") (pin "5") (pinfunction "VREF_5") (pintype "passive"))
    )
    (net (code "123") (name "unconnected-(IC5-IN_C-Pad5)") (class "Default")
      (node (ref "IC5") (pin "5") (pinfunction "IN_C_5") (pintype "bidirectional"))
    )
    (net (code "124") (name "unconnected-(IC5-OUT_C-Pad12)") (class "Default")
      (node (ref "IC5") (pin "12") (pinfunction "OUT_C_12") (pintype "bidirectional"))
    )
    (net (code "125") (name "unconnected-(IC11-~{SHDN}-Pad3)") (class "Default")
      (node (ref "IC11") (pin "3") (pinfunction "~{SHDN}_3") (pintype "passive"))
    )
    (net (code "126") (name "unconnected-(J3-PadP$3)") (class "Default")
      (node (ref "J3") (pin "P$3") (pinfunction "P$3_P$3") (pintype "bidirectional"))
    )
    (net (code "127") (name "unconnected-(PROZ1F-AGND-Pad1)") (class "Default")
      (node (ref "PROZ1") (pin "1") (pinfunction "AGND_1") (pintype "passive"))
    )
    (net (code "128") (name "unconnected-(PROZ1F-VBAT-Pad6)") (class "Default")
      (node (ref "PROZ1") (pin "6") (pinfunction "VBAT_6") (pintype "passive"))
    )
    (net (code "129") (name "unconnected-(PROZ1F-VDDA_IN-Pad2)") (class "Default")
      (node (ref "PROZ1") (pin "2") (pinfunction "VDDA_IN_2") (pintype "passive"))
    )
    (net (code "130") (name "unconnected-(PROZ1F-VDDA_OUT-Pad4)") (class "Default")
      (node (ref "PROZ1") (pin "4") (pinfunction "VDDA_OUT_4") (pintype "passive"))
    )
  )
)
